# Sequencer_-_8_Step_-_Cigar_Box.net
KiCad netlist of a schematic drawn in EAGLE
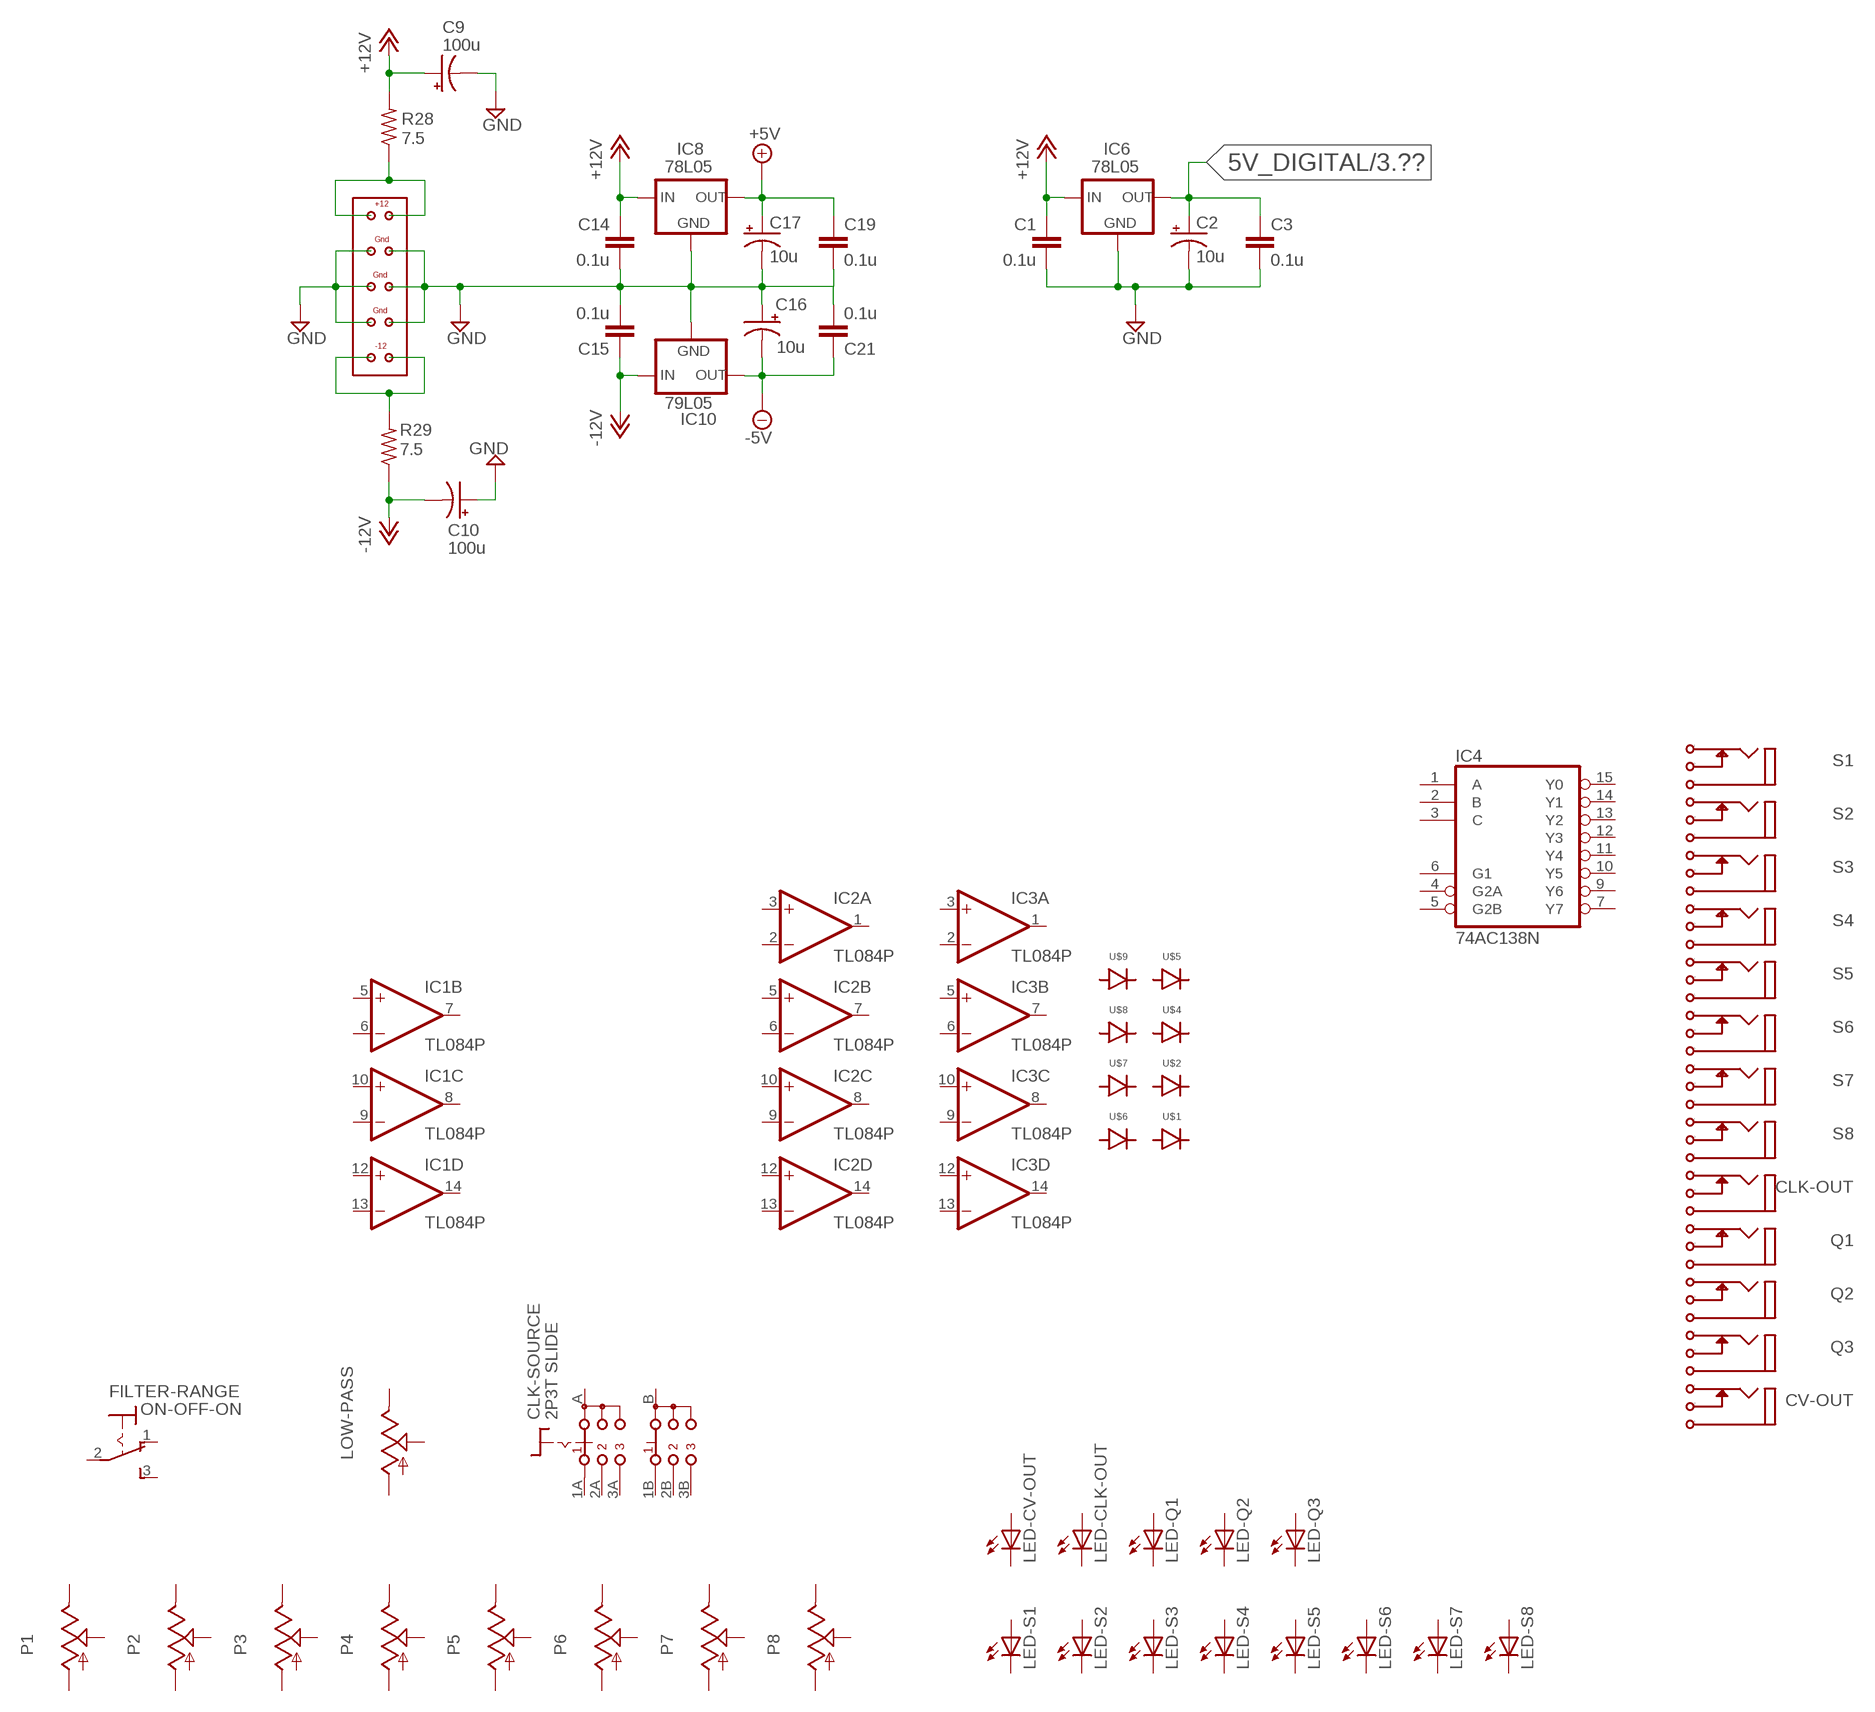
[diagram p0: schematic, sheet 1]
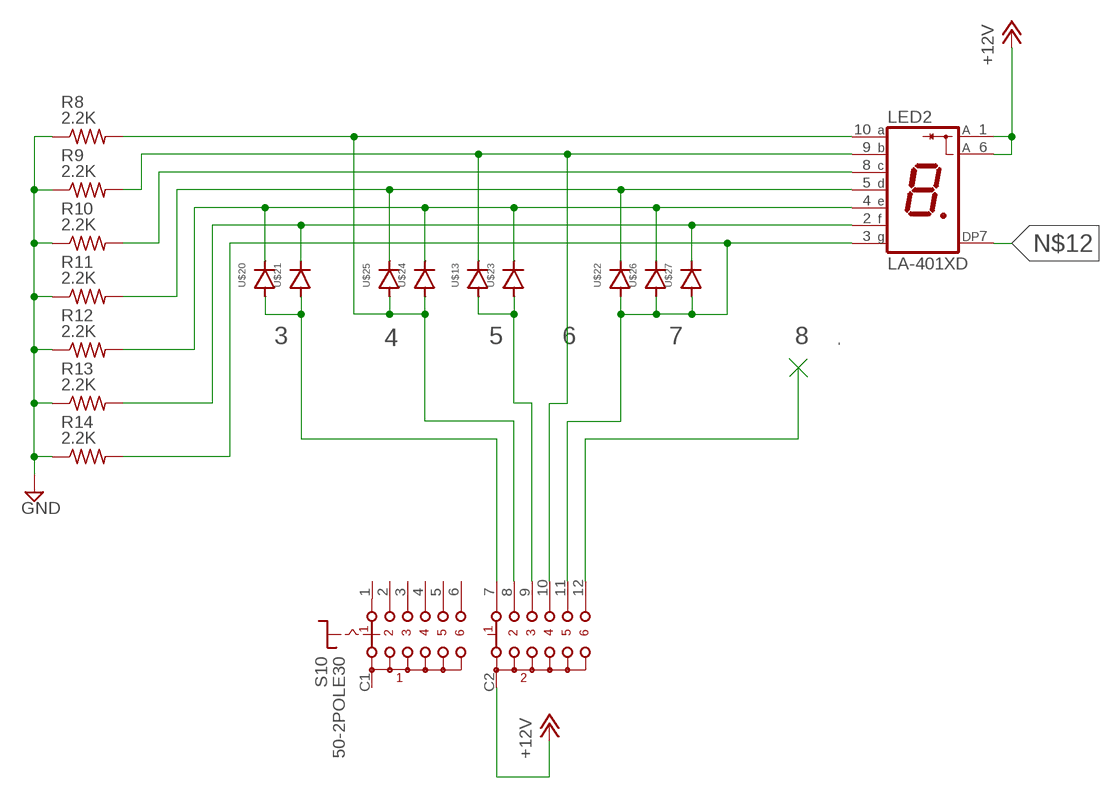
[diagram p1: schematic, sheet 2]
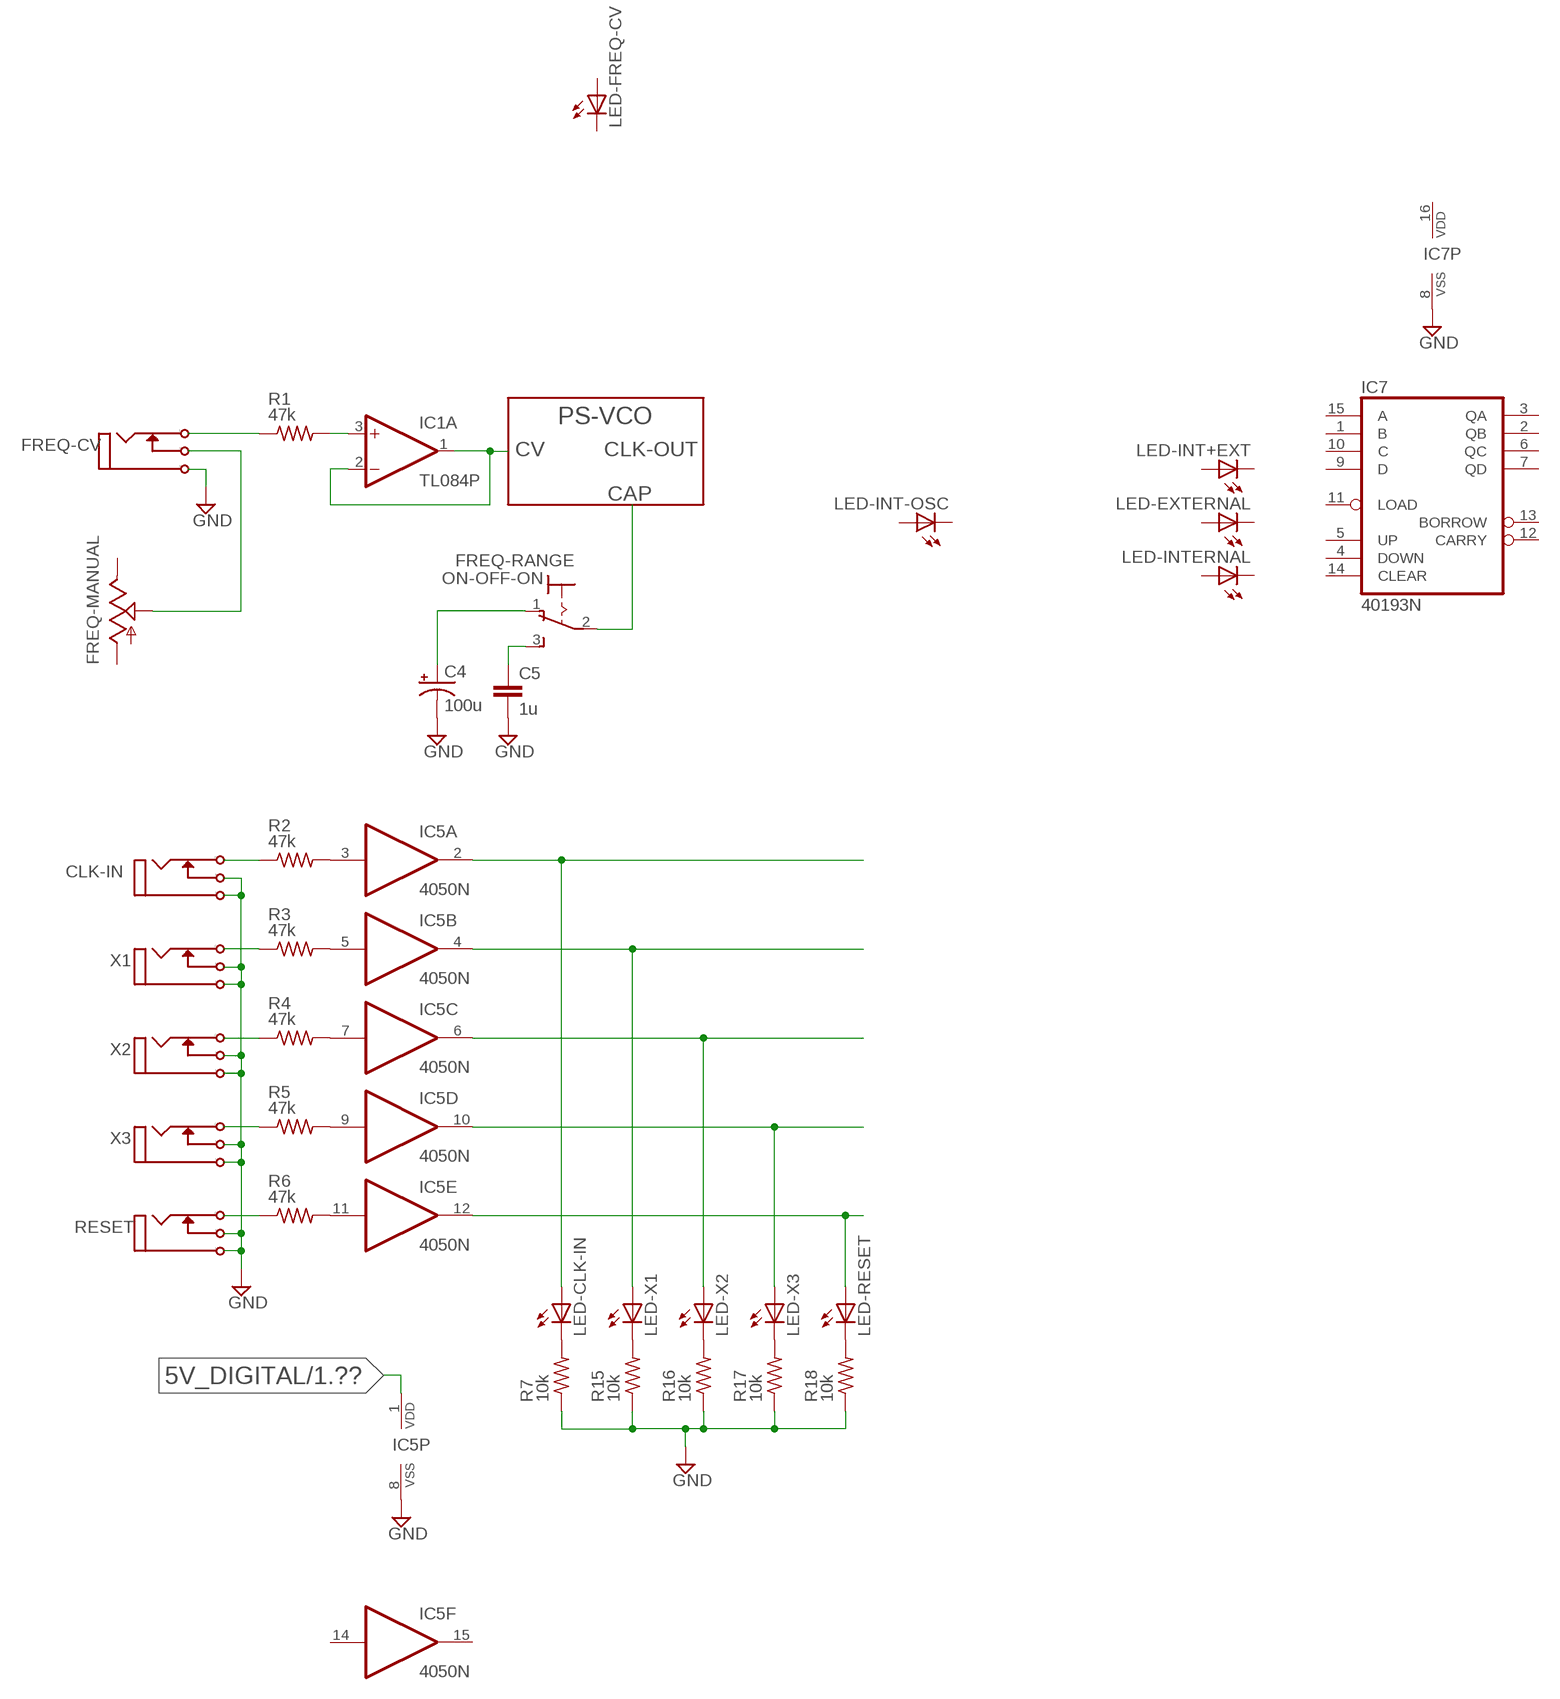
[diagram p2: schematic, sheet 3]

(export (version "E")
  (design (tool "Eeschema 10.0.6"))
  (components
    (comp (ref "LED2")
      (value "LA-401XD")
      (footprint "eagle-import:LA-401")
      (libsource (lib "eagle-import") (part "LA-401DX"))
    )
    (comp (ref "R8")
      (value "2.2K")
      (footprint "eagle-import:R0603")
      (libsource (lib "eagle-import") (part "R-US_R0603"))
    )
    (comp (ref "R9")
      (value "2.2K")
      (footprint "eagle-import:R0603")
      (libsource (lib "eagle-import") (part "R-US_R0603"))
    )
    (comp (ref "R10")
      (value "2.2K")
      (footprint "eagle-import:R0603")
      (libsource (lib "eagle-import") (part "R-US_R0603"))
    )
    (comp (ref "R11")
      (value "2.2K")
      (footprint "eagle-import:R0603")
      (libsource (lib "eagle-import") (part "R-US_R0603"))
    )
    (comp (ref "R12")
      (value "2.2K")
      (footprint "eagle-import:R0603")
      (libsource (lib "eagle-import") (part "R-US_R0603"))
    )
    (comp (ref "R13")
      (value "2.2K")
      (footprint "eagle-import:R0603")
      (libsource (lib "eagle-import") (part "R-US_R0603"))
    )
    (comp (ref "R14")
      (value "2.2K")
      (footprint "eagle-import:R0603")
      (libsource (lib "eagle-import") (part "R-US_R0603"))
    )
    (comp (ref "S10")
      (value "50-2POLE30")
      (footprint "eagle-import:50-2POLE30")
      (libsource (lib "eagle-import") (part "50-2POLE30"))
    )
    (comp (ref "U$13")
      (value "DIODE-0204/5")
      (footprint "eagle-import:DIODE-0204_5")
      (libsource (lib "eagle-import") (part "DIODE-0204/5"))
    )
    (comp (ref "U$20")
      (value "DIODE-0204/5")
      (footprint "eagle-import:DIODE-0204_5")
      (libsource (lib "eagle-import") (part "DIODE-0204/5"))
    )
    (comp (ref "U$21")
      (value "DIODE-0204/5")
      (footprint "eagle-import:DIODE-0204_5")
      (libsource (lib "eagle-import") (part "DIODE-0204/5"))
    )
    (comp (ref "U$22")
      (value "DIODE-0204/5")
      (footprint "eagle-import:DIODE-0204_5")
      (libsource (lib "eagle-import") (part "DIODE-0204/5"))
    )
    (comp (ref "U$23")
      (value "DIODE-0204/5")
      (footprint "eagle-import:DIODE-0204_5")
      (libsource (lib "eagle-import") (part "DIODE-0204/5"))
    )
    (comp (ref "U$24")
      (value "DIODE-0204/5")
      (footprint "eagle-import:DIODE-0204_5")
      (libsource (lib "eagle-import") (part "DIODE-0204/5"))
    )
    (comp (ref "U$25")
      (value "DIODE-0204/5")
      (footprint "eagle-import:DIODE-0204_5")
      (libsource (lib "eagle-import") (part "DIODE-0204/5"))
    )
    (comp (ref "U$26")
      (value "DIODE-0204/5")
      (footprint "eagle-import:DIODE-0204_5")
      (libsource (lib "eagle-import") (part "DIODE-0204/5"))
    )
    (comp (ref "U$27")
      (value "DIODE-0204/5")
      (footprint "eagle-import:DIODE-0204_5")
      (libsource (lib "eagle-import") (part "DIODE-0204/5"))
    )
    (comp (ref "C1")
      (value "0.1u")
      (footprint "eagle-import:C025-050X050")
      (libsource (lib "eagle-import") (part "C-EU025-050X050"))
    )
    (comp (ref "C2")
      (value "10u")
      (footprint "eagle-import:E3,5-10")
      (libsource (lib "eagle-import") (part "CPOL-USE3.5-10"))
    )
    (comp (ref "C3")
      (value "0.1u")
      (footprint "eagle-import:C025-050X050")
      (libsource (lib "eagle-import") (part "C-EU025-050X050"))
    )
    (comp (ref "C9")
      (value "100u")
      (footprint "eagle-import:E3,5-10")
      (libsource (lib "eagle-import") (part "CPOL-USE3.5-10"))
    )
    (comp (ref "C10")
      (value "100u")
      (footprint "eagle-import:E3,5-10")
      (libsource (lib "eagle-import") (part "CPOL-USE3.5-10"))
    )
    (comp (ref "C14")
      (value "0.1u")
      (footprint "eagle-import:C025-050X050")
      (libsource (lib "eagle-import") (part "C-EU025-050X050"))
    )
    (comp (ref "C15")
      (value "0.1u")
      (footprint "eagle-import:C025-050X050")
      (libsource (lib "eagle-import") (part "C-EU025-050X050"))
    )
    (comp (ref "C16")
      (value "10u")
      (footprint "eagle-import:E3,5-10")
      (libsource (lib "eagle-import") (part "CPOL-USE3.5-10"))
    )
    (comp (ref "C17")
      (value "10u")
      (footprint "eagle-import:E3,5-10")
      (libsource (lib "eagle-import") (part "CPOL-USE3.5-10"))
    )
    (comp (ref "C19")
      (value "0.1u")
      (footprint "eagle-import:C025-050X050")
      (libsource (lib "eagle-import") (part "C-EU025-050X050"))
    )
    (comp (ref "C21")
      (value "0.1u")
      (footprint "eagle-import:C025-050X050")
      (libsource (lib "eagle-import") (part "C-EU025-050X050"))
    )
    (comp (ref "CLK-OUT")
      (value "I/O")
      (footprint "eagle-import:MONO_JACK")
      (libsource (lib "eagle-import") (part "MONO_JACK"))
    )
    (comp (ref "CLK-SOURCE")
      (value "2P3T SLIDE")
      (footprint "eagle-import:ELMA-01-2X3")
      (libsource (lib "eagle-import") (part "ELMA-01-2X3"))
    )
    (comp (ref "CV-OUT")
      (value "I/O")
      (footprint "eagle-import:MONO_JACK")
      (libsource (lib "eagle-import") (part "MONO_JACK"))
    )
    (comp (ref "FILTER-RANGE")
      (value "ON-OFF-ON")
      (footprint "eagle-import:320-916")
      (libsource (lib "eagle-import") (part "320-916"))
    )
    (comp (ref "IC1")
      (value "TL084P")
      (footprint "eagle-import:DIL14")
      (libsource (lib "eagle-import") (part "TL084P"))
    )
    (comp (ref "IC2")
      (value "TL084P")
      (footprint "eagle-import:DIL14")
      (libsource (lib "eagle-import") (part "TL084P"))
    )
    (comp (ref "IC3")
      (value "TL084P")
      (footprint "eagle-import:DIL14")
      (libsource (lib "eagle-import") (part "TL084P"))
    )
    (comp (ref "IC4")
      (value "74AC138N")
      (footprint "eagle-import:DIL16")
      (libsource (lib "eagle-import") (part "74138NAC"))
    )
    (comp (ref "IC6")
      (value "78L05")
      (footprint "eagle-import:78LXX")
      (libsource (lib "eagle-import") (part "78LXX"))
    )
    (comp (ref "IC8")
      (value "78L05")
      (footprint "eagle-import:78LXX")
      (libsource (lib "eagle-import") (part "78LXX"))
    )
    (comp (ref "IC10")
      (value "79L05")
      (footprint "eagle-import:79LXX")
      (libsource (lib "eagle-import") (part "79LXX"))
    )
    (comp (ref "LED-CLK-OUT")
      (value "TLLG4400")
      (footprint "eagle-import:LED3MM")
      (fields (field (name "MF") "VISHAY SEMICONDUCTOR"))
      (libsource (lib "eagle-import") (part "TLLG4400"))
    )
    (comp (ref "LED-CV-OUT")
      (value "TLLG4400")
      (footprint "eagle-import:LED3MM")
      (fields (field (name "MF") "VISHAY SEMICONDUCTOR"))
      (libsource (lib "eagle-import") (part "TLLG4400"))
    )
    (comp (ref "LED-Q1")
      (value "TLLG4400")
      (footprint "eagle-import:LED3MM")
      (fields (field (name "MF") "VISHAY SEMICONDUCTOR"))
      (libsource (lib "eagle-import") (part "TLLG4400"))
    )
    (comp (ref "LED-Q2")
      (value "TLLG4400")
      (footprint "eagle-import:LED3MM")
      (fields (field (name "MF") "VISHAY SEMICONDUCTOR"))
      (libsource (lib "eagle-import") (part "TLLG4400"))
    )
    (comp (ref "LED-Q3")
      (value "TLLG4400")
      (footprint "eagle-import:LED3MM")
      (fields (field (name "MF") "VISHAY SEMICONDUCTOR"))
      (libsource (lib "eagle-import") (part "TLLG4400"))
    )
    (comp (ref "LED-S1")
      (value "TLLG4400")
      (footprint "eagle-import:LED3MM")
      (fields (field (name "MF") "VISHAY SEMICONDUCTOR"))
      (libsource (lib "eagle-import") (part "TLLG4400"))
    )
    (comp (ref "LED-S2")
      (value "TLLG4400")
      (footprint "eagle-import:LED3MM")
      (fields (field (name "MF") "VISHAY SEMICONDUCTOR"))
      (libsource (lib "eagle-import") (part "TLLG4400"))
    )
    (comp (ref "LED-S3")
      (value "TLLG4400")
      (footprint "eagle-import:LED3MM")
      (fields (field (name "MF") "VISHAY SEMICONDUCTOR"))
      (libsource (lib "eagle-import") (part "TLLG4400"))
    )
    (comp (ref "LED-S4")
      (value "TLLG4400")
      (footprint "eagle-import:LED3MM")
      (fields (field (name "MF") "VISHAY SEMICONDUCTOR"))
      (libsource (lib "eagle-import") (part "TLLG4400"))
    )
    (comp (ref "LED-S5")
      (value "TLLG4400")
      (footprint "eagle-import:LED3MM")
      (fields (field (name "MF") "VISHAY SEMICONDUCTOR"))
      (libsource (lib "eagle-import") (part "TLLG4400"))
    )
    (comp (ref "LED-S6")
      (value "TLLG4400")
      (footprint "eagle-import:LED3MM")
      (fields (field (name "MF") "VISHAY SEMICONDUCTOR"))
      (libsource (lib "eagle-import") (part "TLLG4400"))
    )
    (comp (ref "LED-S7")
      (value "TLLG4400")
      (footprint "eagle-import:LED3MM")
      (fields (field (name "MF") "VISHAY SEMICONDUCTOR"))
      (libsource (lib "eagle-import") (part "TLLG4400"))
    )
    (comp (ref "LED-S8")
      (value "TLLG4400")
      (footprint "eagle-import:LED3MM")
      (fields (field (name "MF") "VISHAY SEMICONDUCTOR"))
      (libsource (lib "eagle-import") (part "TLLG4400"))
    )
    (comp (ref "LOW-PASS")
      (value "TRIM_US-B64Y")
      (footprint "eagle-import:B64Y")
      (libsource (lib "eagle-import") (part "TRIM_US-B64Y"))
    )
    (comp (ref "P1")
      (value "TRIM_US-B64Y")
      (footprint "eagle-import:B64Y")
      (libsource (lib "eagle-import") (part "TRIM_US-B64Y"))
    )
    (comp (ref "P2")
      (value "TRIM_US-B64Y")
      (footprint "eagle-import:B64Y")
      (libsource (lib "eagle-import") (part "TRIM_US-B64Y"))
    )
    (comp (ref "P3")
      (value "TRIM_US-B64Y")
      (footprint "eagle-import:B64Y")
      (libsource (lib "eagle-import") (part "TRIM_US-B64Y"))
    )
    (comp (ref "P4")
      (value "TRIM_US-B64Y")
      (footprint "eagle-import:B64Y")
      (libsource (lib "eagle-import") (part "TRIM_US-B64Y"))
    )
    (comp (ref "P5")
      (value "TRIM_US-B64Y")
      (footprint "eagle-import:B64Y")
      (libsource (lib "eagle-import") (part "TRIM_US-B64Y"))
    )
    (comp (ref "P6")
      (value "TRIM_US-B64Y")
      (footprint "eagle-import:B64Y")
      (libsource (lib "eagle-import") (part "TRIM_US-B64Y"))
    )
    (comp (ref "P7")
      (value "TRIM_US-B64Y")
      (footprint "eagle-import:B64Y")
      (libsource (lib "eagle-import") (part "TRIM_US-B64Y"))
    )
    (comp (ref "P8")
      (value "TRIM_US-B64Y")
      (footprint "eagle-import:B64Y")
      (libsource (lib "eagle-import") (part "TRIM_US-B64Y"))
    )
    (comp (ref "Q1")
      (value "I/O")
      (footprint "eagle-import:MONO_JACK")
      (libsource (lib "eagle-import") (part "MONO_JACK"))
    )
    (comp (ref "Q2")
      (value "I/O")
      (footprint "eagle-import:MONO_JACK")
      (libsource (lib "eagle-import") (part "MONO_JACK"))
    )
    (comp (ref "Q3")
      (value "I/O")
      (footprint "eagle-import:MONO_JACK")
      (libsource (lib "eagle-import") (part "MONO_JACK"))
    )
    (comp (ref "R28")
      (value "7.5")
      (footprint "eagle-import:0204_7")
      (libsource (lib "eagle-import") (part "resistor_R-US_0204/7"))
    )
    (comp (ref "R29")
      (value "7.5")
      (footprint "eagle-import:0204_7")
      (libsource (lib "eagle-import") (part "resistor_R-US_0204/7"))
    )
    (comp (ref "S1")
      (value "I/O")
      (footprint "eagle-import:MONO_JACK")
      (libsource (lib "eagle-import") (part "MONO_JACK"))
    )
    (comp (ref "S2")
      (value "I/O")
      (footprint "eagle-import:MONO_JACK")
      (libsource (lib "eagle-import") (part "MONO_JACK"))
    )
    (comp (ref "S3")
      (value "I/O")
      (footprint "eagle-import:MONO_JACK")
      (libsource (lib "eagle-import") (part "MONO_JACK"))
    )
    (comp (ref "S4")
      (value "I/O")
      (footprint "eagle-import:MONO_JACK")
      (libsource (lib "eagle-import") (part "MONO_JACK"))
    )
    (comp (ref "S5")
      (value "I/O")
      (footprint "eagle-import:MONO_JACK")
      (libsource (lib "eagle-import") (part "MONO_JACK"))
    )
    (comp (ref "S6")
      (value "I/O")
      (footprint "eagle-import:MONO_JACK")
      (libsource (lib "eagle-import") (part "MONO_JACK"))
    )
    (comp (ref "S7")
      (value "I/O")
      (footprint "eagle-import:MONO_JACK")
      (libsource (lib "eagle-import") (part "MONO_JACK"))
    )
    (comp (ref "S8")
      (value "I/O")
      (footprint "eagle-import:MONO_JACK")
      (libsource (lib "eagle-import") (part "MONO_JACK"))
    )
    (comp (ref "U$1")
      (value "DIODE-0204/5")
      (footprint "eagle-import:DIODE-0204_5")
      (libsource (lib "eagle-import") (part "DIODE-0204/5"))
    )
    (comp (ref "U$2")
      (value "DIODE-0204/5")
      (footprint "eagle-import:DIODE-0204_5")
      (libsource (lib "eagle-import") (part "DIODE-0204/5"))
    )
    (comp (ref "U$4")
      (value "DIODE-0204/5")
      (footprint "eagle-import:DIODE-0204_5")
      (libsource (lib "eagle-import") (part "DIODE-0204/5"))
    )
    (comp (ref "U$5")
      (value "DIODE-0204/5")
      (footprint "eagle-import:DIODE-0204_5")
      (libsource (lib "eagle-import") (part "DIODE-0204/5"))
    )
    (comp (ref "U$6")
      (value "DIODE-0204/5")
      (footprint "eagle-import:DIODE-0204_5")
      (libsource (lib "eagle-import") (part "DIODE-0204/5"))
    )
    (comp (ref "U$7")
      (value "DIODE-0204/5")
      (footprint "eagle-import:DIODE-0204_5")
      (libsource (lib "eagle-import") (part "DIODE-0204/5"))
    )
    (comp (ref "U$8")
      (value "DIODE-0204/5")
      (footprint "eagle-import:DIODE-0204_5")
      (libsource (lib "eagle-import") (part "DIODE-0204/5"))
    )
    (comp (ref "U$9")
      (value "DIODE-0204/5")
      (footprint "eagle-import:DIODE-0204_5")
      (libsource (lib "eagle-import") (part "DIODE-0204/5"))
    )
    (comp (ref "U$10")
      (value "EURORACK-POWER")
      (footprint "eagle-import:EURORACK-POWER")
      (libsource (lib "eagle-import") (part "EURORACK-POWER"))
    )
    (comp (ref "C4")
      (value "100u")
      (footprint "eagle-import:E3,5-10")
      (libsource (lib "eagle-import") (part "CPOL-USE3.5-10"))
    )
    (comp (ref "C5")
      (value "1u")
      (footprint "eagle-import:C025-050X050")
      (libsource (lib "eagle-import") (part "C-EU025-050X050"))
    )
    (comp (ref "CLK-IN")
      (value "I/O")
      (footprint "eagle-import:MONO_JACK")
      (libsource (lib "eagle-import") (part "MONO_JACK"))
    )
    (comp (ref "FREQ-CV")
      (value "I/O")
      (footprint "eagle-import:MONO_JACK")
      (libsource (lib "eagle-import") (part "MONO_JACK"))
    )
    (comp (ref "FREQ-MANUAL")
      (value "TRIM_US-B64Y")
      (footprint "eagle-import:B64Y")
      (libsource (lib "eagle-import") (part "TRIM_US-B64Y"))
    )
    (comp (ref "FREQ-RANGE")
      (value "ON-OFF-ON")
      (footprint "eagle-import:320-916")
      (libsource (lib "eagle-import") (part "320-916"))
    )
    (comp (ref "IC5")
      (value "4050N")
      (footprint "eagle-import:DIL16")
      (libsource (lib "eagle-import") (part "4050N"))
    )
    (comp (ref "IC7")
      (value "40193N")
      (footprint "eagle-import:DIL16")
      (libsource (lib "eagle-import") (part "40193N"))
    )
    (comp (ref "LED-CLK-IN")
      (value "TLLG4400")
      (footprint "eagle-import:LED3MM")
      (fields (field (name "MF") "VISHAY SEMICONDUCTOR"))
      (libsource (lib "eagle-import") (part "TLLG4400"))
    )
    (comp (ref "LED-EXTERNAL")
      (value "TLLG4400")
      (footprint "eagle-import:LED3MM")
      (fields (field (name "MF") "VISHAY SEMICONDUCTOR"))
      (libsource (lib "eagle-import") (part "TLLG4400"))
    )
    (comp (ref "LED-FREQ-CV")
      (value "TLLG4400")
      (footprint "eagle-import:LED3MM")
      (fields (field (name "MF") "VISHAY SEMICONDUCTOR"))
      (libsource (lib "eagle-import") (part "TLLG4400"))
    )
    (comp (ref "LED-INT+EXT")
      (value "TLLG4400")
      (footprint "eagle-import:LED3MM")
      (fields (field (name "MF") "VISHAY SEMICONDUCTOR"))
      (libsource (lib "eagle-import") (part "TLLG4400"))
    )
    (comp (ref "LED-INT-OSC")
      (value "TLLG4400")
      (footprint "eagle-import:LED3MM")
      (fields (field (name "MF") "VISHAY SEMICONDUCTOR"))
      (libsource (lib "eagle-import") (part "TLLG4400"))
    )
    (comp (ref "LED-INTERNAL")
      (value "TLLG4400")
      (footprint "eagle-import:LED3MM")
      (fields (field (name "MF") "VISHAY SEMICONDUCTOR"))
      (libsource (lib "eagle-import") (part "TLLG4400"))
    )
    (comp (ref "LED-RESET")
      (value "TLLG4400")
      (footprint "eagle-import:LED3MM")
      (fields (field (name "MF") "VISHAY SEMICONDUCTOR"))
      (libsource (lib "eagle-import") (part "TLLG4400"))
    )
    (comp (ref "LED-X1")
      (value "TLLG4400")
      (footprint "eagle-import:LED3MM")
      (fields (field (name "MF") "VISHAY SEMICONDUCTOR"))
      (libsource (lib "eagle-import") (part "TLLG4400"))
    )
    (comp (ref "LED-X2")
      (value "TLLG4400")
      (footprint "eagle-import:LED3MM")
      (fields (field (name "MF") "VISHAY SEMICONDUCTOR"))
      (libsource (lib "eagle-import") (part "TLLG4400"))
    )
    (comp (ref "LED-X3")
      (value "TLLG4400")
      (footprint "eagle-import:LED3MM")
      (fields (field (name "MF") "VISHAY SEMICONDUCTOR"))
      (libsource (lib "eagle-import") (part "TLLG4400"))
    )
    (comp (ref "R1")
      (value "47k")
      (footprint "eagle-import:R0603")
      (libsource (lib "eagle-import") (part "R-US_R0603"))
    )
    (comp (ref "R2")
      (value "47k")
      (footprint "eagle-import:R0603")
      (libsource (lib "eagle-import") (part "R-US_R0603"))
    )
    (comp (ref "R3")
      (value "47k")
      (footprint "eagle-import:R0603")
      (libsource (lib "eagle-import") (part "R-US_R0603"))
    )
    (comp (ref "R4")
      (value "47k")
      (footprint "eagle-import:R0603")
      (libsource (lib "eagle-import") (part "R-US_R0603"))
    )
    (comp (ref "R5")
      (value "47k")
      (footprint "eagle-import:R0603")
      (libsource (lib "eagle-import") (part "R-US_R0603"))
    )
    (comp (ref "R6")
      (value "47k")
      (footprint "eagle-import:R0603")
      (libsource (lib "eagle-import") (part "R-US_R0603"))
    )
    (comp (ref "R7")
      (value "10k")
      (footprint "eagle-import:R0603")
      (libsource (lib "eagle-import") (part "R-US_R0603"))
    )
    (comp (ref "R15")
      (value "10k")
      (footprint "eagle-import:R0603")
      (libsource (lib "eagle-import") (part "R-US_R0603"))
    )
    (comp (ref "R16")
      (value "10k")
      (footprint "eagle-import:R0603")
      (libsource (lib "eagle-import") (part "R-US_R0603"))
    )
    (comp (ref "R17")
      (value "10k")
      (footprint "eagle-import:R0603")
      (libsource (lib "eagle-import") (part "R-US_R0603"))
    )
    (comp (ref "R18")
      (value "10k")
      (footprint "eagle-import:R0603")
      (libsource (lib "eagle-import") (part "R-US_R0603"))
    )
    (comp (ref "RESET")
      (value "I/O")
      (footprint "eagle-import:MONO_JACK")
      (libsource (lib "eagle-import") (part "MONO_JACK"))
    )
    (comp (ref "X1")
      (value "I/O")
      (footprint "eagle-import:MONO_JACK")
      (libsource (lib "eagle-import") (part "MONO_JACK"))
    )
    (comp (ref "X2")
      (value "I/O")
      (footprint "eagle-import:MONO_JACK")
      (libsource (lib "eagle-import") (part "MONO_JACK"))
    )
    (comp (ref "X3")
      (value "I/O")
      (footprint "eagle-import:MONO_JACK")
      (libsource (lib "eagle-import") (part "MONO_JACK"))
    )
  )
  (nets
    (net (code "1") (name "+5V") (class "Default")
      (node (ref "C17") (pin "+") (pinfunction "+_+") (pintype "passive"))
      (node (ref "C19") (pin "1") (pinfunction "1_1") (pintype "passive"))
      (node (ref "IC8") (pin "OUT") (pinfunction "OUT_OUT") (pintype "passive"))
    )
    (net (code "2") (name "+12V") (class "Default")
      (node (ref "C1") (pin "1") (pinfunction "1_1") (pintype "passive"))
      (node (ref "C14") (pin "1") (pinfunction "1_1") (pintype "passive"))
      (node (ref "C9") (pin "+") (pinfunction "+_+") (pintype "passive"))
      (node (ref "IC6") (pin "IN") (pinfunction "IN_IN") (pintype "input"))
      (node (ref "IC8") (pin "IN") (pinfunction "IN_IN") (pintype "input"))
      (node (ref "LED2") (pin "1") (pinfunction "A_1") (pintype "passive"))
      (node (ref "LED2") (pin "6") (pinfunction "A_6") (pintype "passive"))
      (node (ref "R28") (pin "2") (pinfunction "2_2") (pintype "passive"))
      (node (ref "S10") (pin "C2") (pinfunction "S2_C2") (pintype "passive"))
    )
    (net (code "3") (name "-5V") (class "Default")
      (node (ref "C16") (pin "-") (pinfunction "-_-") (pintype "passive"))
      (node (ref "C21") (pin "1") (pinfunction "1_1") (pintype "passive"))
      (node (ref "IC10") (pin "OUT") (pinfunction "OUT_OUT") (pintype "passive"))
    )
    (net (code "4") (name "-12V") (class "Default")
      (node (ref "C10") (pin "-") (pinfunction "-_-") (pintype "passive"))
      (node (ref "C15") (pin "1") (pinfunction "1_1") (pintype "passive"))
      (node (ref "IC10") (pin "IN") (pinfunction "IN_IN") (pintype "input"))
      (node (ref "R29") (pin "1") (pinfunction "1_1") (pintype "passive"))
    )
    (net (code "5") (name "5V_DIGITAL") (class "Default")
      (node (ref "C2") (pin "+") (pinfunction "+_+") (pintype "passive"))
      (node (ref "C3") (pin "1") (pinfunction "1_1") (pintype "passive"))
      (node (ref "IC5") (pin "1") (pinfunction "VDD_1") (pintype "power_in"))
      (node (ref "IC6") (pin "OUT") (pinfunction "OUT_OUT") (pintype "passive"))
    )
    (net (code "6") (name "GND") (class "Default")
      (node (ref "C1") (pin "2") (pinfunction "2_2") (pintype "passive"))
      (node (ref "C10") (pin "+") (pinfunction "+_+") (pintype "passive"))
      (node (ref "C14") (pin "2") (pinfunction "2_2") (pintype "passive"))
      (node (ref "C15") (pin "2") (pinfunction "2_2") (pintype "passive"))
      (node (ref "C16") (pin "+") (pinfunction "+_+") (pintype "passive"))
      (node (ref "C17") (pin "-") (pinfunction "-_-") (pintype "passive"))
      (node (ref "C19") (pin "2") (pinfunction "2_2") (pintype "passive"))
      (node (ref "C2") (pin "-") (pinfunction "-_-") (pintype "passive"))
      (node (ref "C21") (pin "2") (pinfunction "2_2") (pintype "passive"))
      (node (ref "C3") (pin "2") (pinfunction "2_2") (pintype "passive"))
      (node (ref "C4") (pin "-") (pinfunction "-_-") (pintype "passive"))
      (node (ref "C5") (pin "2") (pinfunction "2_2") (pintype "passive"))
      (node (ref "C9") (pin "-") (pinfunction "-_-") (pintype "passive"))
      (node (ref "CLK-IN") (pin "P$1") (pinfunction "P$1_P$1") (pintype "bidirectional"))
      (node (ref "CLK-IN") (pin "P$3") (pinfunction "P3_P$3") (pintype "bidirectional"))
      (node (ref "FREQ-CV") (pin "P$1") (pinfunction "P$1_P$1") (pintype "bidirectional"))
      (node (ref "IC10") (pin "GND") (pinfunction "GND_GND") (pintype "input"))
      (node (ref "IC5") (pin "8") (pinfunction "VSS_8") (pintype "power_in"))
      (node (ref "IC6") (pin "GND") (pinfunction "GND_GND") (pintype "input"))
      (node (ref "IC7") (pin "8") (pinfunction "VSS_8") (pintype "power_in"))
      (node (ref "IC8") (pin "GND") (pinfunction "GND_GND") (pintype "input"))
      (node (ref "R10") (pin "1") (pinfunction "1_1") (pintype "passive"))
      (node (ref "R11") (pin "1") (pinfunction "1_1") (pintype "passive"))
      (node (ref "R12") (pin "1") (pinfunction "1_1") (pintype "passive"))
      (node (ref "R13") (pin "1") (pinfunction "1_1") (pintype "passive"))
      (node (ref "R14") (pin "1") (pinfunction "1_1") (pintype "passive"))
      (node (ref "R15") (pin "1") (pinfunction "1_1") (pintype "passive"))
      (node (ref "R16") (pin "1") (pinfunction "1_1") (pintype "passive"))
      (node (ref "R17") (pin "1") (pinfunction "1_1") (pintype "passive"))
      (node (ref "R18") (pin "1") (pinfunction "1_1") (pintype "passive"))
      (node (ref "R7") (pin "1") (pinfunction "1_1") (pintype "passive"))
      (node (ref "R8") (pin "1") (pinfunction "1_1") (pintype "passive"))
      (node (ref "R9") (pin "1") (pinfunction "1_1") (pintype "passive"))
      (node (ref "RESET") (pin "P$1") (pinfunction "P$1_P$1") (pintype "bidirectional"))
      (node (ref "RESET") (pin "P$3") (pinfunction "P3_P$3") (pintype "bidirectional"))
      (node (ref "U$10") (pin "P$3") (pinfunction "P$3_P$3") (pintype "bidirectional"))
      (node (ref "U$10") (pin "P$4") (pinfunction "P$4_P$4") (pintype "bidirectional"))
      (node (ref "U$10") (pin "P$5") (pinfunction "P$5_P$5") (pintype "bidirectional"))
      (node (ref "U$10") (pin "P$6") (pinfunction "P$6_P$6") (pintype "bidirectional"))
      (node (ref "U$10") (pin "P$7") (pinfunction "P$7_P$7") (pintype "bidirectional"))
      (node (ref "U$10") (pin "P$8") (pinfunction "P$8_P$8") (pintype "bidirectional"))
      (node (ref "X1") (pin "P$1") (pinfunction "P$1_P$1") (pintype "bidirectional"))
      (node (ref "X1") (pin "P$3") (pinfunction "P3_P$3") (pintype "bidirectional"))
      (node (ref "X2") (pin "P$1") (pinfunction "P$1_P$1") (pintype "bidirectional"))
      (node (ref "X2") (pin "P$3") (pinfunction "P3_P$3") (pintype "bidirectional"))
      (node (ref "X3") (pin "P$1") (pinfunction "P$1_P$1") (pintype "bidirectional"))
      (node (ref "X3") (pin "P$3") (pinfunction "P3_P$3") (pintype "bidirectional"))
    )
    (net (code "7") (name "N$12") (class "Default")
      (node (ref "LED2") (pin "7") (pinfunction "DP_7") (pintype "passive"))
    )
    (net (code "8") (name "Net-(CLK-IN-P2)") (class "Default")
      (node (ref "CLK-IN") (pin "P$2") (pinfunction "P2_P$2") (pintype "bidirectional"))
      (node (ref "R2") (pin "1") (pinfunction "1_1") (pintype "passive"))
    )
    (net (code "9") (name "Net-(FREQ-CV-P2)") (class "Default")
      (node (ref "FREQ-CV") (pin "P$2") (pinfunction "P2_P$2") (pintype "bidirectional"))
      (node (ref "R1") (pin "1") (pinfunction "1_1") (pintype "passive"))
    )
    (net (code "10") (name "Net-(FREQ-CV-P3)") (class "Default")
      (node (ref "FREQ-CV") (pin "P$3") (pinfunction "P3_P$3") (pintype "bidirectional"))
      (node (ref "FREQ-MANUAL") (pin "S") (pinfunction "S_S") (pintype "passive"))
    )
    (net (code "11") (name "Net-(FREQ-RANGE-O)") (class "Default")
      (node (ref "C4") (pin "+") (pinfunction "+_+") (pintype "passive"))
      (node (ref "FREQ-RANGE") (pin "1") (pinfunction "O_1") (pintype "passive"))
    )
    (net (code "12") (name "Net-(FREQ-RANGE-S)") (class "Default")
      (node (ref "C5") (pin "1") (pinfunction "1_1") (pintype "passive"))
      (node (ref "FREQ-RANGE") (pin "3") (pinfunction "S_3") (pintype "passive"))
    )
    (net (code "13") (name "Net-(IC1A-+IN)") (class "Default")
      (node (ref "IC1") (pin "3") (pinfunction "+IN_3") (pintype "input"))
      (node (ref "R1") (pin "2") (pinfunction "2_2") (pintype "passive"))
    )
    (net (code "14") (name "Net-(IC1A--IN)") (class "Default")
      (node (ref "IC1") (pin "1") (pinfunction "OUT_1") (pintype "output"))
      (node (ref "IC1") (pin "2") (pinfunction "-IN_2") (pintype "input"))
    )
    (net (code "15") (name "Net-(IC5A-I)") (class "Default")
      (node (ref "IC5") (pin "3") (pinfunction "I_3") (pintype "input"))
      (node (ref "R2") (pin "2") (pinfunction "2_2") (pintype "passive"))
    )
    (net (code "16") (name "Net-(IC5A-O)") (class "Default")
      (node (ref "IC5") (pin "2") (pinfunction "O_2") (pintype "output"))
      (node (ref "LED-CLK-IN") (pin "A") (pinfunction "A_A") (pintype "passive"))
    )
    (net (code "17") (name "Net-(IC5B-I)") (class "Default")
      (node (ref "IC5") (pin "5") (pinfunction "I_5") (pintype "input"))
      (node (ref "R3") (pin "2") (pinfunction "2_2") (pintype "passive"))
    )
    (net (code "18") (name "Net-(IC5B-O)") (class "Default")
      (node (ref "IC5") (pin "4") (pinfunction "O_4") (pintype "output"))
      (node (ref "LED-X1") (pin "A") (pinfunction "A_A") (pintype "passive"))
    )
    (net (code "19") (name "Net-(IC5C-I)") (class "Default")
      (node (ref "IC5") (pin "7") (pinfunction "I_7") (pintype "input"))
      (node (ref "R4") (pin "2") (pinfunction "2_2") (pintype "passive"))
    )
    (net (code "20") (name "Net-(IC5C-O)") (class "Default")
      (node (ref "IC5") (pin "6") (pinfunction "O_6") (pintype "output"))
      (node (ref "LED-X2") (pin "A") (pinfunction "A_A") (pintype "passive"))
    )
    (net (code "21") (name "Net-(IC5D-I)") (class "Default")
      (node (ref "IC5") (pin "9") (pinfunction "I_9") (pintype "input"))
      (node (ref "R5") (pin "2") (pinfunction "2_2") (pintype "passive"))
    )
    (net (code "22") (name "Net-(IC5D-O)") (class "Default")
      (node (ref "IC5") (pin "10") (pinfunction "O_10") (pintype "output"))
      (node (ref "LED-X3") (pin "A") (pinfunction "A_A") (pintype "passive"))
    )
    (net (code "23") (name "Net-(IC5E-I)") (class "Default")
      (node (ref "IC5") (pin "11") (pinfunction "I_11") (pintype "input"))
      (node (ref "R6") (pin "2") (pinfunction "2_2") (pintype "passive"))
    )
    (net (code "24") (name "Net-(IC5E-O)") (class "Default")
      (node (ref "IC5") (pin "12") (pinfunction "O_12") (pintype "output"))
      (node (ref "LED-RESET") (pin "A") (pinfunction "A_A") (pintype "passive"))
    )
    (net (code "25") (name "Net-(LED-CLK-IN-C)") (class "Default")
      (node (ref "LED-CLK-IN") (pin "K") (pinfunction "C_K") (pintype "passive"))
      (node (ref "R7") (pin "2") (pinfunction "2_2") (pintype "passive"))
    )
    (net (code "26") (name "Net-(LED-RESET-C)") (class "Default")
      (node (ref "LED-RESET") (pin "K") (pinfunction "C_K") (pintype "passive"))
      (node (ref "R18") (pin "2") (pinfunction "2_2") (pintype "passive"))
    )
    (net (code "27") (name "Net-(LED-X1-C)") (class "Default")
      (node (ref "LED-X1") (pin "K") (pinfunction "C_K") (pintype "passive"))
      (node (ref "R15") (pin "2") (pinfunction "2_2") (pintype "passive"))
    )
    (net (code "28") (name "Net-(LED-X2-C)") (class "Default")
      (node (ref "LED-X2") (pin "K") (pinfunction "C_K") (pintype "passive"))
      (node (ref "R16") (pin "2") (pinfunction "2_2") (pintype "passive"))
    )
    (net (code "29") (name "Net-(LED-X3-C)") (class "Default")
      (node (ref "LED-X3") (pin "K") (pinfunction "C_K") (pintype "passive"))
      (node (ref "R17") (pin "2") (pinfunction "2_2") (pintype "passive"))
    )
    (net (code "30") (name "Net-(LED2-B)") (class "Default")
      (node (ref "LED2") (pin "9") (pinfunction "B_9") (pintype "passive"))
      (node (ref "R9") (pin "2") (pinfunction "2_2") (pintype "passive"))
      (node (ref "S10") (pin "10") (pinfunction "42_10") (pintype "passive"))
      (node (ref "U$13") (pin "CATHODE") (pinfunction "CATHODE_CATHODE") (pintype "bidirectional"))
    )
    (net (code "31") (name "Net-(LED2-C)") (class "Default")
      (node (ref "LED2") (pin "8") (pinfunction "C_8") (pintype "passive"))
      (node (ref "R10") (pin "2") (pinfunction "2_2") (pintype "passive"))
    )
    (net (code "32") (name "Net-(LED2-D)") (class "Default")
      (node (ref "LED2") (pin "5") (pinfunction "D_5") (pintype "passive"))
      (node (ref "R11") (pin "2") (pinfunction "2_2") (pintype "passive"))
      (node (ref "U$22") (pin "CATHODE") (pinfunction "CATHODE_CATHODE") (pintype "bidirectional"))
      (node (ref "U$25") (pin "CATHODE") (pinfunction "CATHODE_CATHODE") (pintype "bidirectional"))
    )
    (net (code "33") (name "Net-(LED2-E)") (class "Default")
      (node (ref "LED2") (pin "4") (pinfunction "E_4") (pintype "passive"))
      (node (ref "R12") (pin "2") (pinfunction "2_2") (pintype "passive"))
      (node (ref "U$20") (pin "CATHODE") (pinfunction "CATHODE_CATHODE") (pintype "bidirectional"))
      (node (ref "U$23") (pin "CATHODE") (pinfunction "CATHODE_CATHODE") (pintype "bidirectional"))
      (node (ref "U$24") (pin "CATHODE") (pinfunction "CATHODE_CATHODE") (pintype "bidirectional"))
      (node (ref "U$26") (pin "CATHODE") (pinfunction "CATHODE_CATHODE") (pintype "bidirectional"))
    )
    (net (code "34") (name "Net-(LED2-F)") (class "Default")
      (node (ref "LED2") (pin "2") (pinfunction "F_2") (pintype "passive"))
      (node (ref "R13") (pin "2") (pinfunction "2_2") (pintype "passive"))
      (node (ref "U$21") (pin "CATHODE") (pinfunction "CATHODE_CATHODE") (pintype "bidirectional"))
      (node (ref "U$27") (pin "CATHODE") (pinfunction "CATHODE_CATHODE") (pintype "bidirectional"))
    )
    (net (code "35") (name "Net-(LED2-G)") (class "Default")
      (node (ref "LED2") (pin "3") (pinfunction "G_3") (pintype "passive"))
      (node (ref "R14") (pin "2") (pinfunction "2_2") (pintype "passive"))
      (node (ref "S10") (pin "11") (pinfunction "52_11") (pintype "passive"))
      (node (ref "U$22") (pin "ANODE") (pinfunction "ANODE_ANODE") (pintype "bidirectional"))
      (node (ref "U$26") (pin "ANODE") (pinfunction "ANODE_ANODE") (pintype "bidirectional"))
      (node (ref "U$27") (pin "ANODE") (pinfunction "ANODE_ANODE") (pintype "bidirectional"))
    )
    (net (code "36") (name "Net-(R28-Pad1)") (class "Default")
      (node (ref "R28") (pin "1") (pinfunction "1_1") (pintype "passive"))
      (node (ref "U$10") (pin "P$1") (pinfunction "P$1_P$1") (pintype "bidirectional"))
      (node (ref "U$10") (pin "P$2") (pinfunction "P$2_P$2") (pintype "bidirectional"))
    )
    (net (code "37") (name "Net-(R29-Pad2)") (class "Default")
      (node (ref "R29") (pin "2") (pinfunction "2_2") (pintype "passive"))
      (node (ref "U$10") (pin "P$10") (pinfunction "P$10_P$10") (pintype "bidirectional"))
      (node (ref "U$10") (pin "P$9") (pinfunction "P$9_P$9") (pintype "bidirectional"))
    )
    (net (code "38") (name "Net-(RESET-P2)") (class "Default")
      (node (ref "R6") (pin "1") (pinfunction "1_1") (pintype "passive"))
      (node (ref "RESET") (pin "P$2") (pinfunction "P2_P$2") (pintype "bidirectional"))
    )
    (net (code "39") (name "Net-(S10-12)") (class "Default")
      (node (ref "S10") (pin "7") (pinfunction "12_7") (pintype "passive"))
      (node (ref "U$20") (pin "ANODE") (pinfunction "ANODE_ANODE") (pintype "bidirectional"))
      (node (ref "U$21") (pin "ANODE") (pinfunction "ANODE_ANODE") (pintype "bidirectional"))
    )
    (net (code "40") (name "Net-(S10-22)") (class "Default")
      (node (ref "LED2") (pin "10") (pinfunction "A_10") (pintype "passive"))
      (node (ref "R8") (pin "2") (pinfunction "2_2") (pintype "passive"))
      (node (ref "S10") (pin "8") (pinfunction "22_8") (pintype "passive"))
      (node (ref "U$24") (pin "ANODE") (pinfunction "ANODE_ANODE") (pintype "bidirectional"))
      (node (ref "U$25") (pin "ANODE") (pinfunction "ANODE_ANODE") (pintype "bidirectional"))
    )
    (net (code "41") (name "Net-(S10-32)") (class "Default")
      (node (ref "S10") (pin "9") (pinfunction "32_9") (pintype "passive"))
      (node (ref "U$13") (pin "ANODE") (pinfunction "ANODE_ANODE") (pintype "bidirectional"))
      (node (ref "U$23") (pin "ANODE") (pinfunction "ANODE_ANODE") (pintype "bidirectional"))
    )
    (net (code "42") (name "Net-(X1-P2)") (class "Default")
      (node (ref "R3") (pin "1") (pinfunction "1_1") (pintype "passive"))
      (node (ref "X1") (pin "P$2") (pinfunction "P2_P$2") (pintype "bidirectional"))
    )
    (net (code "43") (name "Net-(X2-P2)") (class "Default")
      (node (ref "R4") (pin "1") (pinfunction "1_1") (pintype "passive"))
      (node (ref "X2") (pin "P$2") (pinfunction "P2_P$2") (pintype "bidirectional"))
    )
    (net (code "44") (name "Net-(X3-P2)") (class "Default")
      (node (ref "R5") (pin "1") (pinfunction "1_1") (pintype "passive"))
      (node (ref "X3") (pin "P$2") (pinfunction "P2_P$2") (pintype "bidirectional"))
    )
    (net (code "45") (name "VDD") (class "Default")
      (node (ref "IC7") (pin "16") (pinfunction "VDD_16") (pintype "power_in"))
    )
    (net (code "46") (name "unconnected-(CLK-OUT-P2-PadP$2)") (class "Default")
      (node (ref "CLK-OUT") (pin "P$2") (pinfunction "P2_P$2") (pintype "bidirectional"))
    )
    (net (code "47") (name "unconnected-(CLK-OUT-P3-PadP$3)") (class "Default")
      (node (ref "CLK-OUT") (pin "P$3") (pinfunction "P3_P$3") (pintype "bidirectional"))
    )
    (net (code "48") (name "unconnected-(CLK-OUT-PadP$1)") (class "Default")
      (node (ref "CLK-OUT") (pin "P$1") (pinfunction "P$1_P$1") (pintype "bidirectional"))
    )
    (net (code "49") (name "unconnected-(CLK-SOURCE-A1-Pad1A)") (class "Default")
      (node (ref "CLK-SOURCE") (pin "1A") (pinfunction "A1_1A") (pintype "passive"))
    )
    (net (code "50") (name "unconnected-(CLK-SOURCE-A2-Pad2A)") (class "Default")
      (node (ref "CLK-SOURCE") (pin "2A") (pinfunction "A2_2A") (pintype "passive"))
    )
    (net (code "51") (name "unconnected-(CLK-SOURCE-A3-Pad3A)") (class "Default")
      (node (ref "CLK-SOURCE") (pin "3A") (pinfunction "A3_3A") (pintype "passive"))
    )
    (net (code "52") (name "unconnected-(CLK-SOURCE-B1-Pad1B)") (class "Default")
      (node (ref "CLK-SOURCE") (pin "1B") (pinfunction "B1_1B") (pintype "passive"))
    )
    (net (code "53") (name "unconnected-(CLK-SOURCE-B2-Pad2B)") (class "Default")
      (node (ref "CLK-SOURCE") (pin "2B") (pinfunction "B2_2B") (pintype "passive"))
    )
    (net (code "54") (name "unconnected-(CLK-SOURCE-B3-Pad3B)") (class "Default")
      (node (ref "CLK-SOURCE") (pin "3B") (pinfunction "B3_3B") (pintype "passive"))
    )
    (net (code "55") (name "unconnected-(CLK-SOURCE-PadA)") (class "Default")
      (node (ref "CLK-SOURCE") (pin "A") (pinfunction "A_A") (pintype "passive"))
    )
    (net (code "56") (name "unconnected-(CLK-SOURCE-PadB)") (class "Default")
      (node (ref "CLK-SOURCE") (pin "B") (pinfunction "B_B") (pintype "passive"))
    )
    (net (code "57") (name "unconnected-(CV-OUT-P2-PadP$2)") (class "Default")
      (node (ref "CV-OUT") (pin "P$2") (pinfunction "P2_P$2") (pintype "bidirectional"))
    )
    (net (code "58") (name "unconnected-(CV-OUT-P3-PadP$3)") (class "Default")
      (node (ref "CV-OUT") (pin "P$3") (pinfunction "P3_P$3") (pintype "bidirectional"))
    )
    (net (code "59") (name "unconnected-(CV-OUT-PadP$1)") (class "Default")
      (node (ref "CV-OUT") (pin "P$1") (pinfunction "P$1_P$1") (pintype "bidirectional"))
    )
    (net (code "60") (name "unconnected-(FILTER-RANGE-O-Pad1)") (class "Default")
      (node (ref "FILTER-RANGE") (pin "1") (pinfunction "O_1") (pintype "passive"))
    )
    (net (code "61") (name "unconnected-(FILTER-RANGE-P-Pad2)") (class "Default")
      (node (ref "FILTER-RANGE") (pin "2") (pinfunction "P_2") (pintype "passive"))
    )
    (net (code "62") (name "unconnected-(FILTER-RANGE-S-Pad3)") (class "Default")
      (node (ref "FILTER-RANGE") (pin "3") (pinfunction "S_3") (pintype "passive"))
    )
    (net (code "63") (name "unconnected-(FREQ-MANUAL-PadA)") (class "Default")
      (node (ref "FREQ-MANUAL") (pin "A") (pinfunction "A_A") (pintype "passive"))
    )
    (net (code "64") (name "unconnected-(FREQ-MANUAL-PadE)") (class "Default")
      (node (ref "FREQ-MANUAL") (pin "E") (pinfunction "E_E") (pintype "passive"))
    )
    (net (code "65") (name "unconnected-(FREQ-RANGE-P-Pad2)") (class "Default")
      (node (ref "FREQ-RANGE") (pin "2") (pinfunction "P_2") (pintype "passive"))
    )
    (net (code "66") (name "unconnected-(IC1B-+IN-Pad5)") (class "Default")
      (node (ref "IC1") (pin "5") (pinfunction "+IN_5") (pintype "input"))
    )
    (net (code "67") (name "unconnected-(IC1B--IN-Pad6)") (class "Default")
      (node (ref "IC1") (pin "6") (pinfunction "-IN_6") (pintype "input"))
    )
    (net (code "68") (name "unconnected-(IC1B-OUT-Pad7)") (class "Default")
      (node (ref "IC1") (pin "7") (pinfunction "OUT_7") (pintype "output"))
    )
    (net (code "69") (name "unconnected-(IC1C-+IN-Pad10)") (class "Default")
      (node (ref "IC1") (pin "10") (pinfunction "+IN_10") (pintype "input"))
    )
    (net (code "70") (name "unconnected-(IC1C--IN-Pad9)") (class "Default")
      (node (ref "IC1") (pin "9") (pinfunction "-IN_9") (pintype "input"))
    )
    (net (code "71") (name "unconnected-(IC1C-OUT-Pad8)") (class "Default")
      (node (ref "IC1") (pin "8") (pinfunction "OUT_8") (pintype "output"))
    )
    (net (code "72") (name "unconnected-(IC1D-+IN-Pad12)") (class "Default")
      (node (ref "IC1") (pin "12") (pinfunction "+IN_12") (pintype "input"))
    )
    (net (code "73") (name "unconnected-(IC1D--IN-Pad13)") (class "Default")
      (node (ref "IC1") (pin "13") (pinfunction "-IN_13") (pintype "input"))
    )
    (net (code "74") (name "unconnected-(IC1D-OUT-Pad14)") (class "Default")
      (node (ref "IC1") (pin "14") (pinfunction "OUT_14") (pintype "output"))
    )
    (net (code "75") (name "unconnected-(IC2A-+IN-Pad3)") (class "Default")
      (node (ref "IC2") (pin "3") (pinfunction "+IN_3") (pintype "input"))
    )
    (net (code "76") (name "unconnected-(IC2A--IN-Pad2)") (class "Default")
      (node (ref "IC2") (pin "2") (pinfunction "-IN_2") (pintype "input"))
    )
    (net (code "77") (name "unconnected-(IC2A-OUT-Pad1)") (class "Default")
      (node (ref "IC2") (pin "1") (pinfunction "OUT_1") (pintype "output"))
    )
    (net (code "78") (name "unconnected-(IC2B-+IN-Pad5)") (class "Default")
      (node (ref "IC2") (pin "5") (pinfunction "+IN_5") (pintype "input"))
    )
    (net (code "79") (name "unconnected-(IC2B--IN-Pad6)") (class "Default")
      (node (ref "IC2") (pin "6") (pinfunction "-IN_6") (pintype "input"))
    )
    (net (code "80") (name "unconnected-(IC2B-OUT-Pad7)") (class "Default")
      (node (ref "IC2") (pin "7") (pinfunction "OUT_7") (pintype "output"))
    )
    (net (code "81") (name "unconnected-(IC2C-+IN-Pad10)") (class "Default")
      (node (ref "IC2") (pin "10") (pinfunction "+IN_10") (pintype "input"))
    )
    (net (code "82") (name "unconnected-(IC2C--IN-Pad9)") (class "Default")
      (node (ref "IC2") (pin "9") (pinfunction "-IN_9") (pintype "input"))
    )
    (net (code "83") (name "unconnected-(IC2C-OUT-Pad8)") (class "Default")
      (node (ref "IC2") (pin "8") (pinfunction "OUT_8") (pintype "output"))
    )
    (net (code "84") (name "unconnected-(IC2D-+IN-Pad12)") (class "Default")
      (node (ref "IC2") (pin "12") (pinfunction "+IN_12") (pintype "input"))
    )
    (net (code "85") (name "unconnected-(IC2D--IN-Pad13)") (class "Default")
      (node (ref "IC2") (pin "13") (pinfunction "-IN_13") (pintype "input"))
    )
    (net (code "86") (name "unconnected-(IC2D-OUT-Pad14)") (class "Default")
      (node (ref "IC2") (pin "14") (pinfunction "OUT_14") (pintype "output"))
    )
    (net (code "87") (name "unconnected-(IC3A-+IN-Pad3)") (class "Default")
      (node (ref "IC3") (pin "3") (pinfunction "+IN_3") (pintype "input"))
    )
    (net (code "88") (name "unconnected-(IC3A--IN-Pad2)") (class "Default")
      (node (ref "IC3") (pin "2") (pinfunction "-IN_2") (pintype "input"))
    )
    (net (code "89") (name "unconnected-(IC3A-OUT-Pad1)") (class "Default")
      (node (ref "IC3") (pin "1") (pinfunction "OUT_1") (pintype "output"))
    )
    (net (code "90") (name "unconnected-(IC3B-+IN-Pad5)") (class "Default")
      (node (ref "IC3") (pin "5") (pinfunction "+IN_5") (pintype "input"))
    )
    (net (code "91") (name "unconnected-(IC3B--IN-Pad6)") (class "Default")
      (node (ref "IC3") (pin "6") (pinfunction "-IN_6") (pintype "input"))
    )
    (net (code "92") (name "unconnected-(IC3B-OUT-Pad7)") (class "Default")
      (node (ref "IC3") (pin "7") (pinfunction "OUT_7") (pintype "output"))
    )
    (net (code "93") (name "unconnected-(IC3C-+IN-Pad10)") (class "Default")
      (node (ref "IC3") (pin "10") (pinfunction "+IN_10") (pintype "input"))
    )
    (net (code "94") (name "unconnected-(IC3C--IN-Pad9)") (class "Default")
      (node (ref "IC3") (pin "9") (pinfunction "-IN_9") (pintype "input"))
    )
    (net (code "95") (name "unconnected-(IC3C-OUT-Pad8)") (class "Default")
      (node (ref "IC3") (pin "8") (pinfunction "OUT_8") (pintype "output"))
    )
    (net (code "96") (name "unconnected-(IC3D-+IN-Pad12)") (class "Default")
      (node (ref "IC3") (pin "12") (pinfunction "+IN_12") (pintype "input"))
    )
    (net (code "97") (name "unconnected-(IC3D--IN-Pad13)") (class "Default")
      (node (ref "IC3") (pin "13") (pinfunction "-IN_13") (pintype "input"))
    )
    (net (code "98") (name "unconnected-(IC3D-OUT-Pad14)") (class "Default")
      (node (ref "IC3") (pin "14") (pinfunction "OUT_14") (pintype "output"))
    )
    (net (code "99") (name "unconnected-(IC4A-A-Pad1)") (class "Default")
      (node (ref "IC4") (pin "1") (pinfunction "A_1") (pintype "input"))
    )
    (net (code "100") (name "unconnected-(IC4A-B-Pad2)") (class "Default")
      (node (ref "IC4") (pin "2") (pinfunction "B_2") (pintype "input"))
    )
    (net (code "101") (name "unconnected-(IC4A-C-Pad3)") (class "Default")
      (node (ref "IC4") (pin "3") (pinfunction "C_3") (pintype "input"))
    )
    (net (code "102") (name "unconnected-(IC4A-G1-Pad6)") (class "Default")
      (node (ref "IC4") (pin "6") (pinfunction "G1_6") (pintype "input"))
    )
    (net (code "103") (name "unconnected-(IC4A-G2A-Pad4)") (class "Default")
      (node (ref "IC4") (pin "4") (pinfunction "G2A_4") (pintype "input"))
    )
    (net (code "104") (name "unconnected-(IC4A-G2B-Pad5)") (class "Default")
      (node (ref "IC4") (pin "5") (pinfunction "G2B_5") (pintype "input"))
    )
    (net (code "105") (name "unconnected-(IC4A-Y0-Pad15)") (class "Default")
      (node (ref "IC4") (pin "15") (pinfunction "Y0_15") (pintype "output"))
    )
    (net (code "106") (name "unconnected-(IC4A-Y1-Pad14)") (class "Default")
      (node (ref "IC4") (pin "14") (pinfunction "Y1_14") (pintype "output"))
    )
    (net (code "107") (name "unconnected-(IC4A-Y2-Pad13)") (class "Default")
      (node (ref "IC4") (pin "13") (pinfunction "Y2_13") (pintype "output"))
    )
    (net (code "108") (name "unconnected-(IC4A-Y3-Pad12)") (class "Default")
      (node (ref "IC4") (pin "12") (pinfunction "Y3_12") (pintype "output"))
    )
    (net (code "109") (name "unconnected-(IC4A-Y4-Pad11)") (class "Default")
      (node (ref "IC4") (pin "11") (pinfunction "Y4_11") (pintype "output"))
    )
    (net (code "110") (name "unconnected-(IC4A-Y5-Pad10)") (class "Default")
      (node (ref "IC4") (pin "10") (pinfunction "Y5_10") (pintype "output"))
    )
    (net (code "111") (name "unconnected-(IC4A-Y6-Pad9)") (class "Default")
      (node (ref "IC4") (pin "9") (pinfunction "Y6_9") (pintype "output"))
    )
    (net (code "112") (name "unconnected-(IC4A-Y7-Pad7)") (class "Default")
      (node (ref "IC4") (pin "7") (pinfunction "Y7_7") (pintype "output"))
    )
    (net (code "113") (name "unconnected-(IC5F-I-Pad14)") (class "Default")
      (node (ref "IC5") (pin "14") (pinfunction "I_14") (pintype "input"))
    )
    (net (code "114") (name "unconnected-(IC5F-O-Pad15)") (class "Default")
      (node (ref "IC5") (pin "15") (pinfunction "O_15") (pintype "output"))
    )
    (net (code "115") (name "unconnected-(IC7A-A-Pad15)") (class "Default")
      (node (ref "IC7") (pin "15") (pinfunction "A_15") (pintype "input"))
    )
    (net (code "116") (name "unconnected-(IC7A-B-Pad1)") (class "Default")
      (node (ref "IC7") (pin "1") (pinfunction "B_1") (pintype "input"))
    )
    (net (code "117") (name "unconnected-(IC7A-BORROW-Pad13)") (class "Default")
      (node (ref "IC7") (pin "13") (pinfunction "BORROW_13") (pintype "output"))
    )
    (net (code "118") (name "unconnected-(IC7A-C-Pad10)") (class "Default")
      (node (ref "IC7") (pin "10") (pinfunction "C_10") (pintype "input"))
    )
    (net (code "119") (name "unconnected-(IC7A-CARRY-Pad12)") (class "Default")
      (node (ref "IC7") (pin "12") (pinfunction "CARRY_12") (pintype "output"))
    )
    (net (code "120") (name "unconnected-(IC7A-CLEAR-Pad14)") (class "Default")
      (node (ref "IC7") (pin "14") (pinfunction "CLEAR_14") (pintype "input"))
    )
    (net (code "121") (name "unconnected-(IC7A-D-Pad9)") (class "Default")
      (node (ref "IC7") (pin "9") (pinfunction "D_9") (pintype "input"))
    )
    (net (code "122") (name "unconnected-(IC7A-DOWN-Pad4)") (class "Default")
      (node (ref "IC7") (pin "4") (pinfunction "DOWN_4") (pintype "input"))
    )
    (net (code "123") (name "unconnected-(IC7A-LOAD-Pad11)") (class "Default")
      (node (ref "IC7") (pin "11") (pinfunction "LOAD_11") (pintype "input"))
    )
    (net (code "124") (name "unconnected-(IC7A-QA-Pad3)") (class "Default")
      (node (ref "IC7") (pin "3") (pinfunction "QA_3") (pintype "output"))
    )
    (net (code "125") (name "unconnected-(IC7A-QB-Pad2)") (class "Default")
      (node (ref "IC7") (pin "2") (pinfunction "QB_2") (pintype "output"))
    )
    (net (code "126") (name "unconnected-(IC7A-QC-Pad6)") (class "Default")
      (node (ref "IC7") (pin "6") (pinfunction "QC_6") (pintype "output"))
    )
    (net (code "127") (name "unconnected-(IC7A-QD-Pad7)") (class "Default")
      (node (ref "IC7") (pin "7") (pinfunction "QD_7") (pintype "output"))
    )
    (net (code "128") (name "unconnected-(IC7A-UP-Pad5)") (class "Default")
      (node (ref "IC7") (pin "5") (pinfunction "UP_5") (pintype "input"))
    )
    (net (code "129") (name "unconnected-(LED-CLK-OUT-C-PadK)") (class "Default")
      (node (ref "LED-CLK-OUT") (pin "K") (pinfunction "C_K") (pintype "passive"))
    )
    (net (code "130") (name "unconnected-(LED-CLK-OUT-PadA)") (class "Default")
      (node (ref "LED-CLK-OUT") (pin "A") (pinfunction "A_A") (pintype "passive"))
    )
    (net (code "131") (name "unconnected-(LED-CV-OUT-C-PadK)") (class "Default")
      (node (ref "LED-CV-OUT") (pin "K") (pinfunction "C_K") (pintype "passive"))
    )
    (net (code "132") (name "unconnected-(LED-CV-OUT-PadA)") (class "Default")
      (node (ref "LED-CV-OUT") (pin "A") (pinfunction "A_A") (pintype "passive"))
    )
    (net (code "133") (name "unconnected-(LED-EXTERNAL-C-PadK)") (class "Default")
      (node (ref "LED-EXTERNAL") (pin "K") (pinfunction "C_K") (pintype "passive"))
    )
    (net (code "134") (name "unconnected-(LED-EXTERNAL-PadA)") (class "Default")
      (node (ref "LED-EXTERNAL") (pin "A") (pinfunction "A_A") (pintype "passive"))
    )
    (net (code "135") (name "unconnected-(LED-FREQ-CV-C-PadK)") (class "Default")
      (node (ref "LED-FREQ-CV") (pin "K") (pinfunction "C_K") (pintype "passive"))
    )
    (net (code "136") (name "unconnected-(LED-FREQ-CV-PadA)") (class "Default")
      (node (ref "LED-FREQ-CV") (pin "A") (pinfunction "A_A") (pintype "passive"))
    )
    (net (code "137") (name "unconnected-(LED-INT+EXT-C-PadK)") (class "Default")
      (node (ref "LED-INT+EXT") (pin "K") (pinfunction "C_K") (pintype "passive"))
    )
    (net (code "138") (name "unconnected-(LED-INT+EXT-PadA)") (class "Default")
      (node (ref "LED-INT+EXT") (pin "A") (pinfunction "A_A") (pintype "passive"))
    )
    (net (code "139") (name "unconnected-(LED-INT-OSC-C-PadK)") (class "Default")
      (node (ref "LED-INT-OSC") (pin "K") (pinfunction "C_K") (pintype "passive"))
    )
    (net (code "140") (name "unconnected-(LED-INT-OSC-PadA)") (class "Default")
      (node (ref "LED-INT-OSC") (pin "A") (pinfunction "A_A") (pintype "passive"))
    )
    (net (code "141") (name "unconnected-(LED-INTERNAL-C-PadK)") (class "Default")
      (node (ref "LED-INTERNAL") (pin "K") (pinfunction "C_K") (pintype "passive"))
    )
    (net (code "142") (name "unconnected-(LED-INTERNAL-PadA)") (class "Default")
      (node (ref "LED-INTERNAL") (pin "A") (pinfunction "A_A") (pintype "passive"))
    )
    (net (code "143") (name "unconnected-(LED-Q1-C-PadK)") (class "Default")
      (node (ref "LED-Q1") (pin "K") (pinfunction "C_K") (pintype "passive"))
    )
    (net (code "144") (name "unconnected-(LED-Q1-PadA)") (class "Default")
      (node (ref "LED-Q1") (pin "A") (pinfunction "A_A") (pintype "passive"))
    )
    (net (code "145") (name "unconnected-(LED-Q2-C-PadK)") (class "Default")
      (node (ref "LED-Q2") (pin "K") (pinfunction "C_K") (pintype "passive"))
    )
    (net (code "146") (name "unconnected-(LED-Q2-PadA)") (class "Default")
      (node (ref "LED-Q2") (pin "A") (pinfunction "A_A") (pintype "passive"))
    )
    (net (code "147") (name "unconnected-(LED-Q3-C-PadK)") (class "Default")
      (node (ref "LED-Q3") (pin "K") (pinfunction "C_K") (pintype "passive"))
    )
    (net (code "148") (name "unconnected-(LED-Q3-PadA)") (class "Default")
      (node (ref "LED-Q3") (pin "A") (pinfunction "A_A") (pintype "passive"))
    )
    (net (code "149") (name "unconnected-(LED-S1-C-PadK)") (class "Default")
      (node (ref "LED-S1") (pin "K") (pinfunction "C_K") (pintype "passive"))
    )
    (net (code "150") (name "unconnected-(LED-S1-PadA)") (class "Default")
      (node (ref "LED-S1") (pin "A") (pinfunction "A_A") (pintype "passive"))
    )
    (net (code "151") (name "unconnected-(LED-S2-C-PadK)") (class "Default")
      (node (ref "LED-S2") (pin "K") (pinfunction "C_K") (pintype "passive"))
    )
    (net (code "152") (name "unconnected-(LED-S2-PadA)") (class "Default")
      (node (ref "LED-S2") (pin "A") (pinfunction "A_A") (pintype "passive"))
    )
    (net (code "153") (name "unconnected-(LED-S3-C-PadK)") (class "Default")
      (node (ref "LED-S3") (pin "K") (pinfunction "C_K") (pintype "passive"))
    )
    (net (code "154") (name "unconnected-(LED-S3-PadA)") (class "Default")
      (node (ref "LED-S3") (pin "A") (pinfunction "A_A") (pintype "passive"))
    )
    (net (code "155") (name "unconnected-(LED-S4-C-PadK)") (class "Default")
      (node (ref "LED-S4") (pin "K") (pinfunction "C_K") (pintype "passive"))
    )
    (net (code "156") (name "unconnected-(LED-S4-PadA)") (class "Default")
      (node (ref "LED-S4") (pin "A") (pinfunction "A_A") (pintype "passive"))
    )
    (net (code "157") (name "unconnected-(LED-S5-C-PadK)") (class "Default")
      (node (ref "LED-S5") (pin "K") (pinfunction "C_K") (pintype "passive"))
    )
    (net (code "158") (name "unconnected-(LED-S5-PadA)") (class "Default")
      (node (ref "LED-S5") (pin "A") (pinfunction "A_A") (pintype "passive"))
    )
    (net (code "159") (name "unconnected-(LED-S6-C-PadK)") (class "Default")
      (node (ref "LED-S6") (pin "K") (pinfunction "C_K") (pintype "passive"))
    )
    (net (code "160") (name "unconnected-(LED-S6-PadA)") (class "Default")
      (node (ref "LED-S6") (pin "A") (pinfunction "A_A") (pintype "passive"))
    )
    (net (code "161") (name "unconnected-(LED-S7-C-PadK)") (class "Default")
      (node (ref "LED-S7") (pin "K") (pinfunction "C_K") (pintype "passive"))
    )
    (net (code "162") (name "unconnected-(LED-S7-PadA)") (class "Default")
      (node (ref "LED-S7") (pin "A") (pinfunction "A_A") (pintype "passive"))
    )
    (net (code "163") (name "unconnected-(LED-S8-C-PadK)") (class "Default")
      (node (ref "LED-S8") (pin "K") (pinfunction "C_K") (pintype "passive"))
    )
    (net (code "164") (name "unconnected-(LED-S8-PadA)") (class "Default")
      (node (ref "LED-S8") (pin "A") (pinfunction "A_A") (pintype "passive"))
    )
    (net (code "165") (name "unconnected-(LOW-PASS-PadA)") (class "Default")
      (node (ref "LOW-PASS") (pin "A") (pinfunction "A_A") (pintype "passive"))
    )
    (net (code "166") (name "unconnected-(LOW-PASS-PadE)") (class "Default")
      (node (ref "LOW-PASS") (pin "E") (pinfunction "E_E") (pintype "passive"))
    )
    (net (code "167") (name "unconnected-(LOW-PASS-PadS)") (class "Default")
      (node (ref "LOW-PASS") (pin "S") (pinfunction "S_S") (pintype "passive"))
    )
    (net (code "168") (name "unconnected-(P1-PadA)") (class "Default")
      (node (ref "P1") (pin "A") (pinfunction "A_A") (pintype "passive"))
    )
    (net (code "169") (name "unconnected-(P1-PadE)") (class "Default")
      (node (ref "P1") (pin "E") (pinfunction "E_E") (pintype "passive"))
    )
    (net (code "170") (name "unconnected-(P1-PadS)") (class "Default")
      (node (ref "P1") (pin "S") (pinfunction "S_S") (pintype "passive"))
    )
    (net (code "171") (name "unconnected-(P2-PadA)") (class "Default")
      (node (ref "P2") (pin "A") (pinfunction "A_A") (pintype "passive"))
    )
    (net (code "172") (name "unconnected-(P2-PadE)") (class "Default")
      (node (ref "P2") (pin "E") (pinfunction "E_E") (pintype "passive"))
    )
    (net (code "173") (name "unconnected-(P2-PadS)") (class "Default")
      (node (ref "P2") (pin "S") (pinfunction "S_S") (pintype "passive"))
    )
    (net (code "174") (name "unconnected-(P3-PadA)") (class "Default")
      (node (ref "P3") (pin "A") (pinfunction "A_A") (pintype "passive"))
    )
    (net (code "175") (name "unconnected-(P3-PadE)") (class "Default")
      (node (ref "P3") (pin "E") (pinfunction "E_E") (pintype "passive"))
    )
    (net (code "176") (name "unconnected-(P3-PadS)") (class "Default")
      (node (ref "P3") (pin "S") (pinfunction "S_S") (pintype "passive"))
    )
    (net (code "177") (name "unconnected-(P4-PadA)") (class "Default")
      (node (ref "P4") (pin "A") (pinfunction "A_A") (pintype "passive"))
    )
    (net (code "178") (name "unconnected-(P4-PadE)") (class "Default")
      (node (ref "P4") (pin "E") (pinfunction "E_E") (pintype "passive"))
    )
    (net (code "179") (name "unconnected-(P4-PadS)") (class "Default")
      (node (ref "P4") (pin "S") (pinfunction "S_S") (pintype "passive"))
    )
    (net (code "180") (name "unconnected-(P5-PadA)") (class "Default")
      (node (ref "P5") (pin "A") (pinfunction "A_A") (pintype "passive"))
    )
    (net (code "181") (name "unconnected-(P5-PadE)") (class "Default")
      (node (ref "P5") (pin "E") (pinfunction "E_E") (pintype "passive"))
    )
    (net (code "182") (name "unconnected-(P5-PadS)") (class "Default")
      (node (ref "P5") (pin "S") (pinfunction "S_S") (pintype "passive"))
    )
    (net (code "183") (name "unconnected-(P6-PadA)") (class "Default")
      (node (ref "P6") (pin "A") (pinfunction "A_A") (pintype "passive"))
    )
    (net (code "184") (name "unconnected-(P6-PadE)") (class "Default")
      (node (ref "P6") (pin "E") (pinfunction "E_E") (pintype "passive"))
    )
    (net (code "185") (name "unconnected-(P6-PadS)") (class "Default")
      (node (ref "P6") (pin "S") (pinfunction "S_S") (pintype "passive"))
    )
    (net (code "186") (name "unconnected-(P7-PadA)") (class "Default")
      (node (ref "P7") (pin "A") (pinfunction "A_A") (pintype "passive"))
    )
    (net (code "187") (name "unconnected-(P7-PadE)") (class "Default")
      (node (ref "P7") (pin "E") (pinfunction "E_E") (pintype "passive"))
    )
    (net (code "188") (name "unconnected-(P7-PadS)") (class "Default")
      (node (ref "P7") (pin "S") (pinfunction "S_S") (pintype "passive"))
    )
    (net (code "189") (name "unconnected-(P8-PadA)") (class "Default")
      (node (ref "P8") (pin "A") (pinfunction "A_A") (pintype "passive"))
    )
    (net (code "190") (name "unconnected-(P8-PadE)") (class "Default")
      (node (ref "P8") (pin "E") (pinfunction "E_E") (pintype "passive"))
    )
    (net (code "191") (name "unconnected-(P8-PadS)") (class "Default")
      (node (ref "P8") (pin "S") (pinfunction "S_S") (pintype "passive"))
    )
    (net (code "192") (name "unconnected-(Q1-P2-PadP$2)") (class "Default")
      (node (ref "Q1") (pin "P$2") (pinfunction "P2_P$2") (pintype "bidirectional"))
    )
    (net (code "193") (name "unconnected-(Q1-P3-PadP$3)") (class "Default")
      (node (ref "Q1") (pin "P$3") (pinfunction "P3_P$3") (pintype "bidirectional"))
    )
    (net (code "194") (name "unconnected-(Q1-PadP$1)") (class "Default")
      (node (ref "Q1") (pin "P$1") (pinfunction "P$1_P$1") (pintype "bidirectional"))
    )
    (net (code "195") (name "unconnected-(Q2-P2-PadP$2)") (class "Default")
      (node (ref "Q2") (pin "P$2") (pinfunction "P2_P$2") (pintype "bidirectional"))
    )
    (net (code "196") (name "unconnected-(Q2-P3-PadP$3)") (class "Default")
      (node (ref "Q2") (pin "P$3") (pinfunction "P3_P$3") (pintype "bidirectional"))
    )
    (net (code "197") (name "unconnected-(Q2-PadP$1)") (class "Default")
      (node (ref "Q2") (pin "P$1") (pinfunction "P$1_P$1") (pintype "bidirectional"))
    )
    (net (code "198") (name "unconnected-(Q3-P2-PadP$2)") (class "Default")
      (node (ref "Q3") (pin "P$2") (pinfunction "P2_P$2") (pintype "bidirectional"))
    )
    (net (code "199") (name "unconnected-(Q3-P3-PadP$3)") (class "Default")
      (node (ref "Q3") (pin "P$3") (pinfunction "P3_P$3") (pintype "bidirectional"))
    )
    (net (code "200") (name "unconnected-(Q3-PadP$1)") (class "Default")
      (node (ref "Q3") (pin "P$1") (pinfunction "P$1_P$1") (pintype "bidirectional"))
    )
    (net (code "201") (name "unconnected-(S1-P2-PadP$2)") (class "Default")
      (node (ref "S1") (pin "P$2") (pinfunction "P2_P$2") (pintype "bidirectional"))
    )
    (net (code "202") (name "unconnected-(S1-P3-PadP$3)") (class "Default")
      (node (ref "S1") (pin "P$3") (pinfunction "P3_P$3") (pintype "bidirectional"))
    )
    (net (code "203") (name "unconnected-(S1-PadP$1)") (class "Default")
      (node (ref "S1") (pin "P$1") (pinfunction "P$1_P$1") (pintype "bidirectional"))
    )
    (net (code "204") (name "unconnected-(S2-P2-PadP$2)") (class "Default")
      (node (ref "S2") (pin "P$2") (pinfunction "P2_P$2") (pintype "bidirectional"))
    )
    (net (code "205") (name "unconnected-(S2-P3-PadP$3)") (class "Default")
      (node (ref "S2") (pin "P$3") (pinfunction "P3_P$3") (pintype "bidirectional"))
    )
    (net (code "206") (name "unconnected-(S2-PadP$1)") (class "Default")
      (node (ref "S2") (pin "P$1") (pinfunction "P$1_P$1") (pintype "bidirectional"))
    )
    (net (code "207") (name "unconnected-(S3-P2-PadP$2)") (class "Default")
      (node (ref "S3") (pin "P$2") (pinfunction "P2_P$2") (pintype "bidirectional"))
    )
    (net (code "208") (name "unconnected-(S3-P3-PadP$3)") (class "Default")
      (node (ref "S3") (pin "P$3") (pinfunction "P3_P$3") (pintype "bidirectional"))
    )
    (net (code "209") (name "unconnected-(S3-PadP$1)") (class "Default")
      (node (ref "S3") (pin "P$1") (pinfunction "P$1_P$1") (pintype "bidirectional"))
    )
    (net (code "210") (name "unconnected-(S4-P2-PadP$2)") (class "Default")
      (node (ref "S4") (pin "P$2") (pinfunction "P2_P$2") (pintype "bidirectional"))
    )
    (net (code "211") (name "unconnected-(S4-P3-PadP$3)") (class "Default")
      (node (ref "S4") (pin "P$3") (pinfunction "P3_P$3") (pintype "bidirectional"))
    )
    (net (code "212") (name "unconnected-(S4-PadP$1)") (class "Default")
      (node (ref "S4") (pin "P$1") (pinfunction "P$1_P$1") (pintype "bidirectional"))
    )
    (net (code "213") (name "unconnected-(S5-P2-PadP$2)") (class "Default")
      (node (ref "S5") (pin "P$2") (pinfunction "P2_P$2") (pintype "bidirectional"))
    )
    (net (code "214") (name "unconnected-(S5-P3-PadP$3)") (class "Default")
      (node (ref "S5") (pin "P$3") (pinfunction "P3_P$3") (pintype "bidirectional"))
    )
    (net (code "215") (name "unconnected-(S5-PadP$1)") (class "Default")
      (node (ref "S5") (pin "P$1") (pinfunction "P$1_P$1") (pintype "bidirectional"))
    )
    (net (code "216") (name "unconnected-(S6-P2-PadP$2)") (class "Default")
      (node (ref "S6") (pin "P$2") (pinfunction "P2_P$2") (pintype "bidirectional"))
    )
    (net (code "217") (name "unconnected-(S6-P3-PadP$3)") (class "Default")
      (node (ref "S6") (pin "P$3") (pinfunction "P3_P$3") (pintype "bidirectional"))
    )
    (net (code "218") (name "unconnected-(S6-PadP$1)") (class "Default")
      (node (ref "S6") (pin "P$1") (pinfunction "P$1_P$1") (pintype "bidirectional"))
    )
    (net (code "219") (name "unconnected-(S7-P2-PadP$2)") (class "Default")
      (node (ref "S7") (pin "P$2") (pinfunction "P2_P$2") (pintype "bidirectional"))
    )
    (net (code "220") (name "unconnected-(S7-P3-PadP$3)") (class "Default")
      (node (ref "S7") (pin "P$3") (pinfunction "P3_P$3") (pintype "bidirectional"))
    )
    (net (code "221") (name "unconnected-(S7-PadP$1)") (class "Default")
      (node (ref "S7") (pin "P$1") (pinfunction "P$1_P$1") (pintype "bidirectional"))
    )
    (net (code "222") (name "unconnected-(S8-P2-PadP$2)") (class "Default")
      (node (ref "S8") (pin "P$2") (pinfunction "P2_P$2") (pintype "bidirectional"))
    )
    (net (code "223") (name "unconnected-(S8-P3-PadP$3)") (class "Default")
      (node (ref "S8") (pin "P$3") (pinfunction "P3_P$3") (pintype "bidirectional"))
    )
    (net (code "224") (name "unconnected-(S8-PadP$1)") (class "Default")
      (node (ref "S8") (pin "P$1") (pinfunction "P$1_P$1") (pintype "bidirectional"))
    )
    (net (code "225") (name "unconnected-(S10-11-Pad1)") (class "Default")
      (node (ref "S10") (pin "1") (pinfunction "11_1") (pintype "passive"))
    )
    (net (code "226") (name "unconnected-(S10-21-Pad2)") (class "Default")
      (node (ref "S10") (pin "2") (pinfunction "21_2") (pintype "passive"))
    )
    (net (code "227") (name "unconnected-(S10-31-Pad3)") (class "Default")
      (node (ref "S10") (pin "3") (pinfunction "31_3") (pintype "passive"))
    )
    (net (code "228") (name "unconnected-(S10-41-Pad4)") (class "Default")
      (node (ref "S10") (pin "4") (pinfunction "41_4") (pintype "passive"))
    )
    (net (code "229") (name "unconnected-(S10-51-Pad5)") (class "Default")
      (node (ref "S10") (pin "5") (pinfunction "51_5") (pintype "passive"))
    )
    (net (code "230") (name "unconnected-(S10-61-Pad6)") (class "Default")
      (node (ref "S10") (pin "6") (pinfunction "61_6") (pintype "passive"))
    )
    (net (code "231") (name "unconnected-(S10-62-Pad12)") (class "Default")
      (node (ref "S10") (pin "12") (pinfunction "62_12") (pintype "passive"))
    )
    (net (code "232") (name "unconnected-(S10-S1-PadC1)") (class "Default")
      (node (ref "S10") (pin "C1") (pinfunction "S1_C1") (pintype "passive"))
    )
    (net (code "233") (name "unconnected-(U$1-PadANODE)") (class "Default")
      (node (ref "U$1") (pin "ANODE") (pinfunction "ANODE_ANODE") (pintype "bidirectional"))
    )
    (net (code "234") (name "unconnected-(U$1-PadCATHODE)") (class "Default")
      (node (ref "U$1") (pin "CATHODE") (pinfunction "CATHODE_CATHODE") (pintype "bidirectional"))
    )
    (net (code "235") (name "unconnected-(U$2-PadANODE)") (class "Default")
      (node (ref "U$2") (pin "ANODE") (pinfunction "ANODE_ANODE") (pintype "bidirectional"))
    )
    (net (code "236") (name "unconnected-(U$2-PadCATHODE)") (class "Default")
      (node (ref "U$2") (pin "CATHODE") (pinfunction "CATHODE_CATHODE") (pintype "bidirectional"))
    )
    (net (code "237") (name "unconnected-(U$4-PadANODE)") (class "Default")
      (node (ref "U$4") (pin "ANODE") (pinfunction "ANODE_ANODE") (pintype "bidirectional"))
    )
    (net (code "238") (name "unconnected-(U$4-PadCATHODE)") (class "Default")
      (node (ref "U$4") (pin "CATHODE") (pinfunction "CATHODE_CATHODE") (pintype "bidirectional"))
    )
    (net (code "239") (name "unconnected-(U$5-PadANODE)") (class "Default")
      (node (ref "U$5") (pin "ANODE") (pinfunction "ANODE_ANODE") (pintype "bidirectional"))
    )
    (net (code "240") (name "unconnected-(U$5-PadCATHODE)") (class "Default")
      (node (ref "U$5") (pin "CATHODE") (pinfunction "CATHODE_CATHODE") (pintype "bidirectional"))
    )
    (net (code "241") (name "unconnected-(U$6-PadANODE)") (class "Default")
      (node (ref "U$6") (pin "ANODE") (pinfunction "ANODE_ANODE") (pintype "bidirectional"))
    )
    (net (code "242") (name "unconnected-(U$6-PadCATHODE)") (class "Default")
      (node (ref "U$6") (pin "CATHODE") (pinfunction "CATHODE_CATHODE") (pintype "bidirectional"))
    )
    (net (code "243") (name "unconnected-(U$7-PadANODE)") (class "Default")
      (node (ref "U$7") (pin "ANODE") (pinfunction "ANODE_ANODE") (pintype "bidirectional"))
    )
    (net (code "244") (name "unconnected-(U$7-PadCATHODE)") (class "Default")
      (node (ref "U$7") (pin "CATHODE") (pinfunction "CATHODE_CATHODE") (pintype "bidirectional"))
    )
    (net (code "245") (name "unconnected-(U$8-PadANODE)") (class "Default")
      (node (ref "U$8") (pin "ANODE") (pinfunction "ANODE_ANODE") (pintype "bidirectional"))
    )
    (net (code "246") (name "unconnected-(U$8-PadCATHODE)") (class "Default")
      (node (ref "U$8") (pin "CATHODE") (pinfunction "CATHODE_CATHODE") (pintype "bidirectional"))
    )
    (net (code "247") (name "unconnected-(U$9-PadANODE)") (class "Default")
      (node (ref "U$9") (pin "ANODE") (pinfunction "ANODE_ANODE") (pintype "bidirectional"))
    )
    (net (code "248") (name "unconnected-(U$9-PadCATHODE)") (class "Default")
      (node (ref "U$9") (pin "CATHODE") (pinfunction "CATHODE_CATHODE") (pintype "bidirectional"))
    )
  )
)
